# opendeck_mini.net
KiCad netlist of a schematic drawn in EAGLE
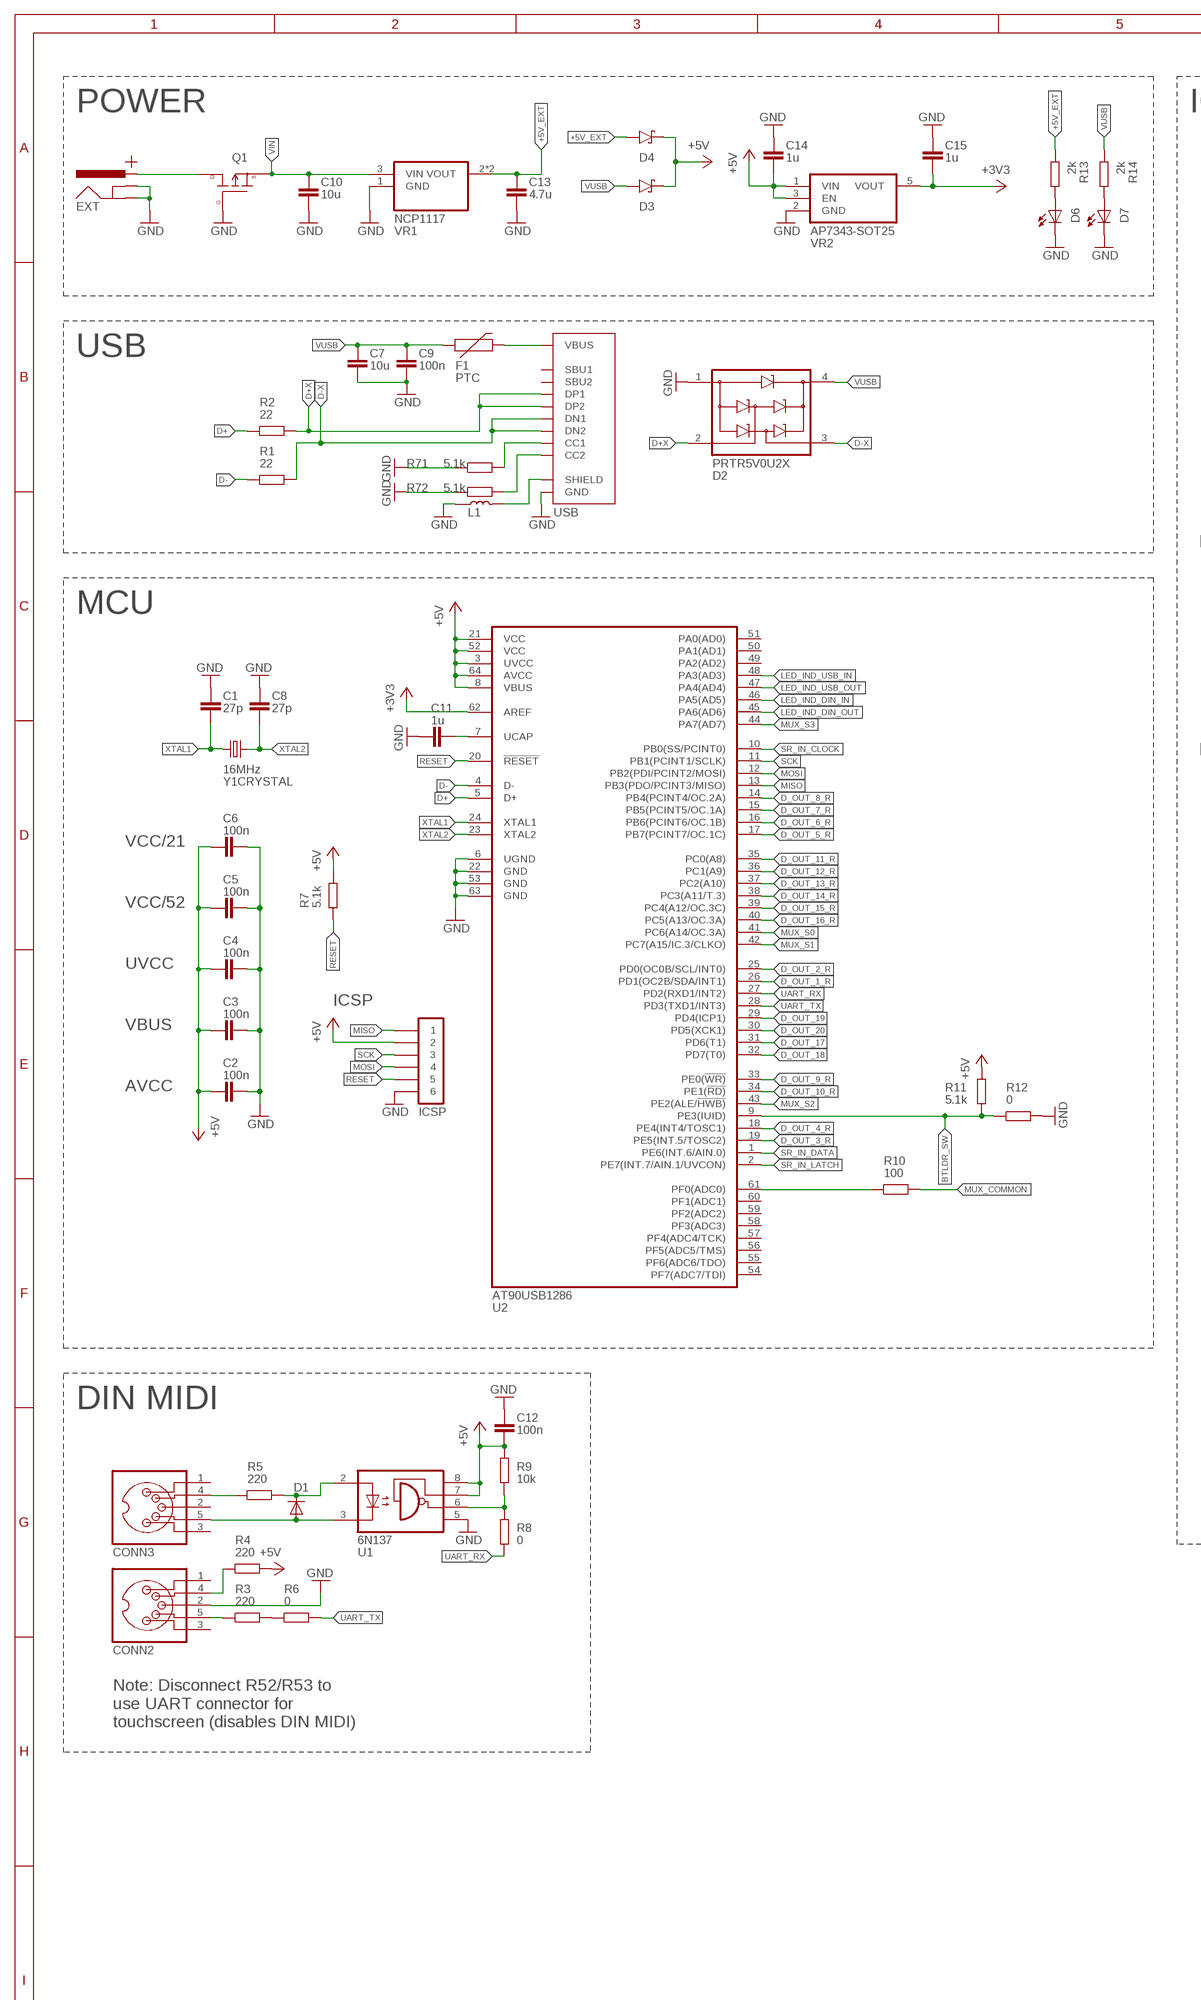
[diagram p0: schematic, sheet 1, part 1 of 2]
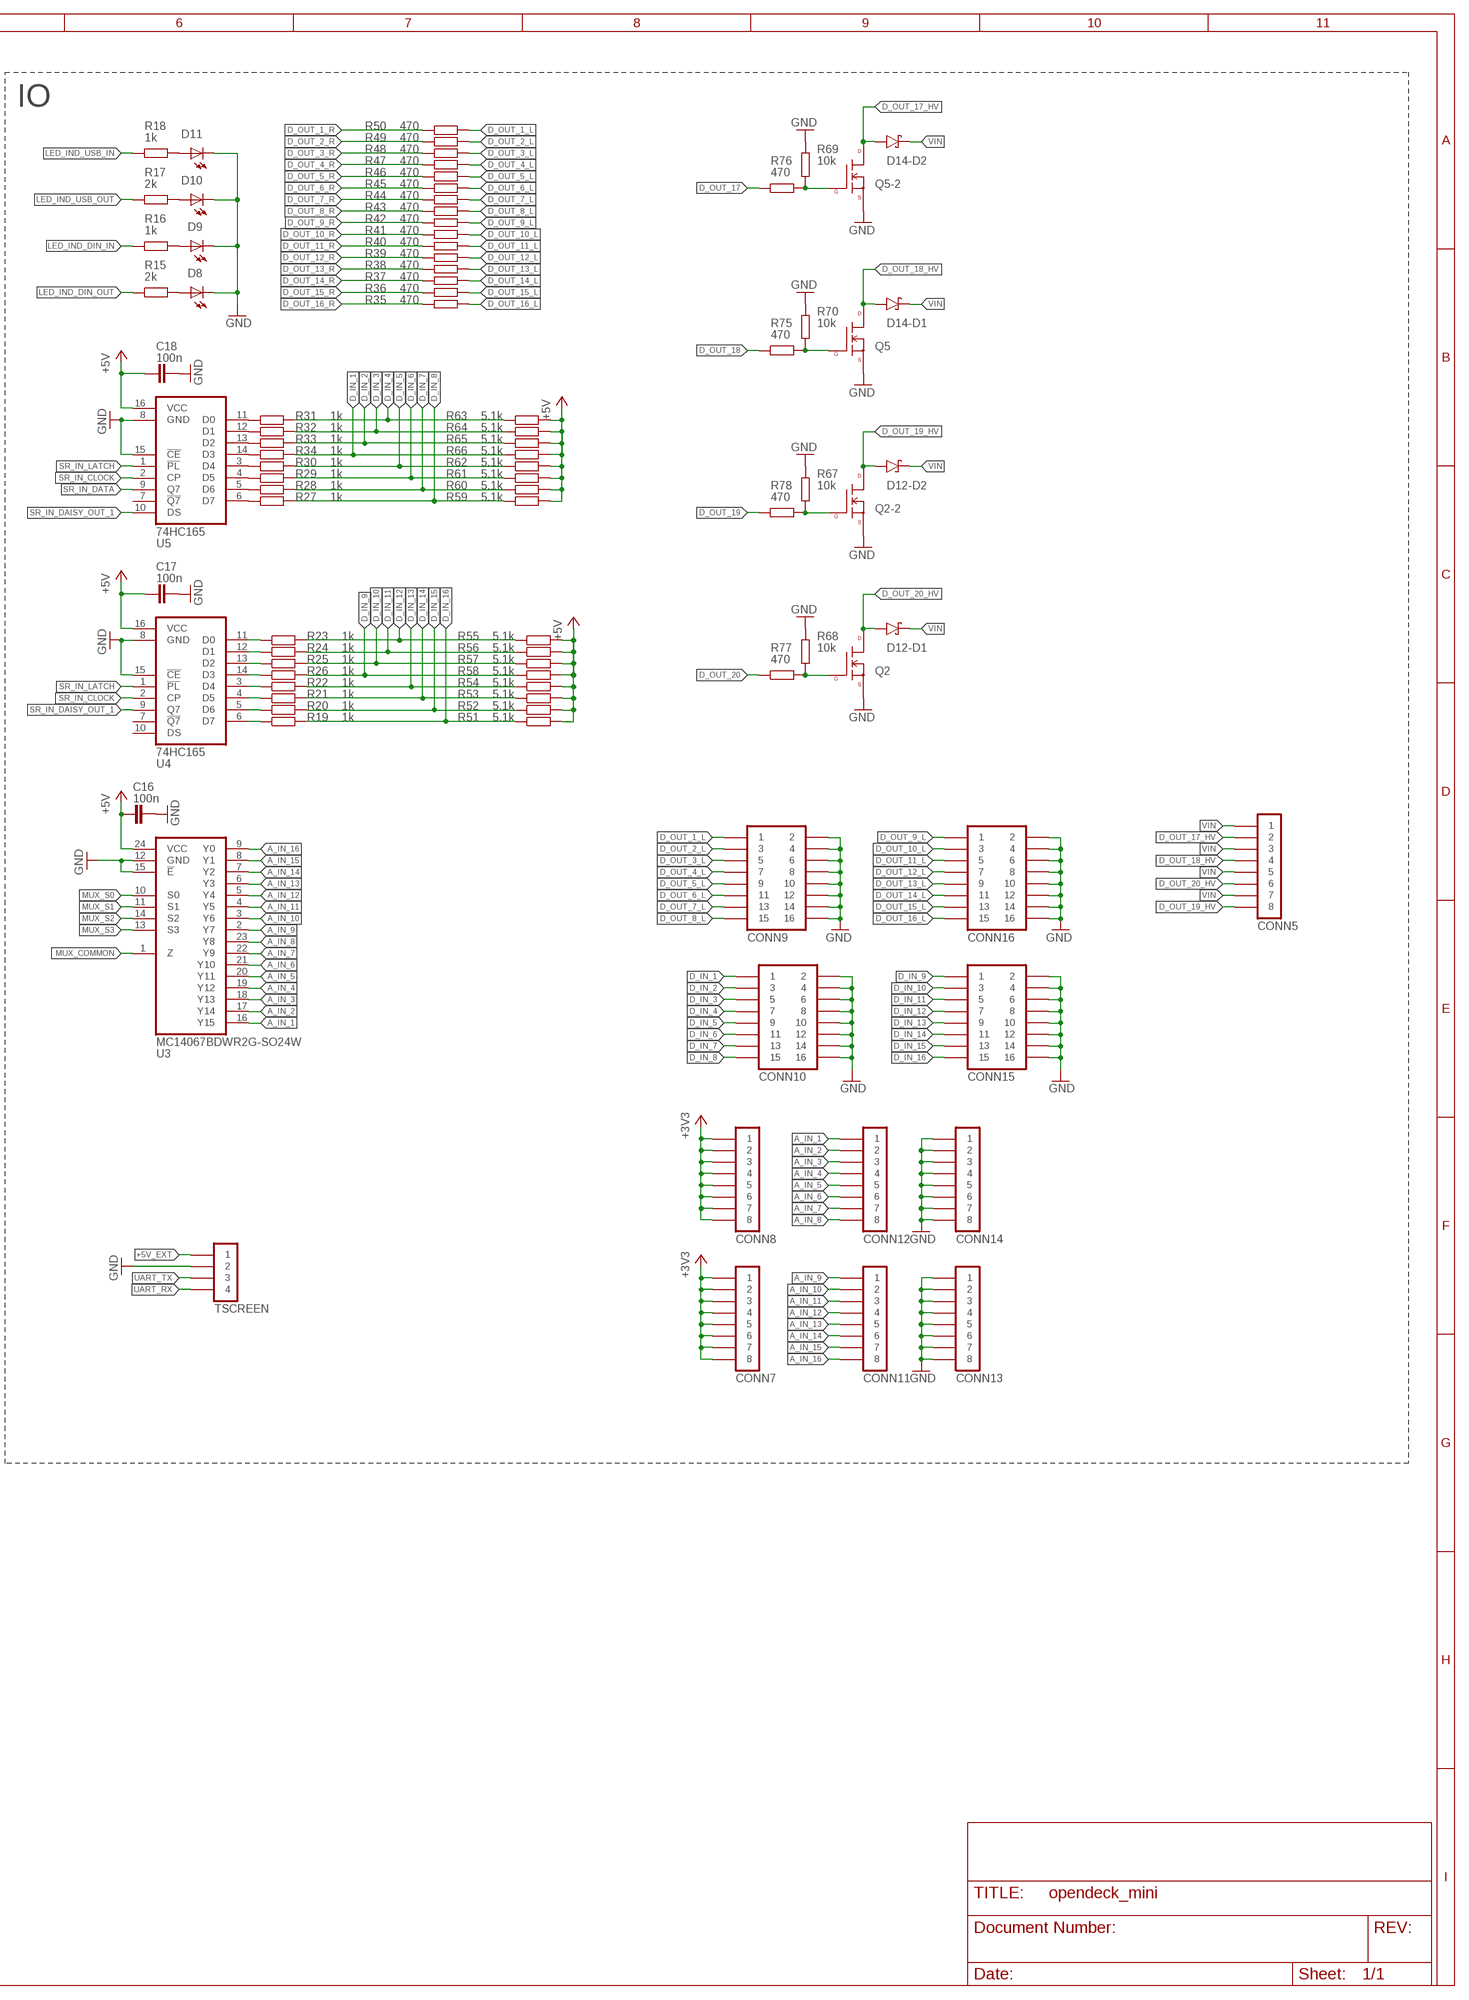
[diagram p1: schematic, sheet 1, part 2 of 2]

(export (version "E")
  (design (tool "Eeschema 10.0.6"))
  (components
    (comp (ref "C1")
      (value "27p")
      (footprint "eagle-import:C0402")
      (libsource (lib "eagle-import") (part "CAPACITOR-0402"))
    )
    (comp (ref "C2")
      (value "100n")
      (footprint "eagle-import:C0402")
      (libsource (lib "eagle-import") (part "CAPACITOR-0402"))
    )
    (comp (ref "C3")
      (value "100n")
      (footprint "eagle-import:C0402")
      (libsource (lib "eagle-import") (part "CAPACITOR-0402"))
    )
    (comp (ref "C4")
      (value "100n")
      (footprint "eagle-import:C0402")
      (libsource (lib "eagle-import") (part "CAPACITOR-0402"))
    )
    (comp (ref "C5")
      (value "100n")
      (footprint "eagle-import:C0402")
      (libsource (lib "eagle-import") (part "CAPACITOR-0402"))
    )
    (comp (ref "C6")
      (value "100n")
      (footprint "eagle-import:C0402")
      (libsource (lib "eagle-import") (part "CAPACITOR-0402"))
    )
    (comp (ref "C7")
      (value "10u")
      (footprint "eagle-import:C0805")
      (libsource (lib "eagle-import") (part "CAPACITOR-0805"))
    )
    (comp (ref "C8")
      (value "27p")
      (footprint "eagle-import:C0402")
      (libsource (lib "eagle-import") (part "CAPACITOR-0402"))
    )
    (comp (ref "C9")
      (value "100n")
      (footprint "eagle-import:C0402")
      (libsource (lib "eagle-import") (part "CAPACITOR-0402"))
    )
    (comp (ref "C10")
      (value "10u")
      (footprint "eagle-import:C0805")
      (libsource (lib "eagle-import") (part "CAPACITOR-0805"))
    )
    (comp (ref "C11")
      (value "1u")
      (footprint "eagle-import:C0603")
      (libsource (lib "eagle-import") (part "CAPACITOR-0603"))
    )
    (comp (ref "C12")
      (value "100n")
      (footprint "eagle-import:C0402")
      (libsource (lib "eagle-import") (part "CAPACITOR-0402"))
    )
    (comp (ref "C13")
      (value "4.7u")
      (footprint "eagle-import:C0603")
      (libsource (lib "eagle-import") (part "CAPACITOR-0603"))
    )
    (comp (ref "C14")
      (value "1u")
      (footprint "eagle-import:C0603")
      (libsource (lib "eagle-import") (part "CAPACITOR-0603"))
    )
    (comp (ref "C15")
      (value "1u")
      (footprint "eagle-import:C0603")
      (libsource (lib "eagle-import") (part "CAPACITOR-0603"))
    )
    (comp (ref "C16")
      (value "100n")
      (footprint "eagle-import:C0402")
      (libsource (lib "eagle-import") (part "CAPACITOR-0402"))
    )
    (comp (ref "C17")
      (value "100n")
      (footprint "eagle-import:C0402")
      (libsource (lib "eagle-import") (part "CAPACITOR-0402"))
    )
    (comp (ref "C18")
      (value "100n")
      (footprint "eagle-import:C0402")
      (libsource (lib "eagle-import") (part "CAPACITOR-0402"))
    )
    (comp (ref "CONN2")
      (value "MIDI_CONN-STD")
      (footprint "eagle-import:DIN5")
      (fields (field (name "MANUFACTURER") "Switchcraft") (field (name "MPN") "57PC5F"))
      (libsource (lib "eagle-import") (part "MIDI_CONN-STD"))
    )
    (comp (ref "CONN3")
      (value "MIDI_CONN-STD")
      (footprint "eagle-import:DIN5")
      (fields (field (name "MANUFACTURER") "Switchcraft") (field (name "MPN") "57PC5F"))
      (libsource (lib "eagle-import") (part "MIDI_CONN-STD"))
    )
    (comp (ref "CONN5")
      (value "PINHD-1X08")
      (footprint "eagle-import:PHOENIX_CONTACT-1984675")
      (fields (field (name "MANUFACTURER") "Phoenix Contact") (field (name "MPN") "1984675"))
      (libsource (lib "eagle-import") (part "PINHD-1X08"))
    )
    (comp (ref "CONN7")
      (value "PINHD-1X08-TH-2.54MM")
      (footprint "eagle-import:1X08-2.54")
      (libsource (lib "eagle-import") (part "PINHD-1X08-TH-2.54MM"))
    )
    (comp (ref "CONN8")
      (value "PINHD-1X08-TH-2.54MM")
      (footprint "eagle-import:1X08-2.54")
      (libsource (lib "eagle-import") (part "PINHD-1X08-TH-2.54MM"))
    )
    (comp (ref "CONN9")
      (value "PINHD-2X08-TH-2.54MM")
      (footprint "eagle-import:2X08-2.54")
      (libsource (lib "eagle-import") (part "PINHD-2X08-TH-2.54MM"))
    )
    (comp (ref "CONN10")
      (value "PINHD-2X08-TH-2.54MM")
      (footprint "eagle-import:2X08-2.54")
      (libsource (lib "eagle-import") (part "PINHD-2X08-TH-2.54MM"))
    )
    (comp (ref "CONN11")
      (value "PINHD-1X08-TH-2.54MM")
      (footprint "eagle-import:1X08-2.54")
      (libsource (lib "eagle-import") (part "PINHD-1X08-TH-2.54MM"))
    )
    (comp (ref "CONN12")
      (value "PINHD-1X08-TH-2.54MM")
      (footprint "eagle-import:1X08-2.54")
      (libsource (lib "eagle-import") (part "PINHD-1X08-TH-2.54MM"))
    )
    (comp (ref "CONN13")
      (value "PINHD-1X08-TH-2.54MM")
      (footprint "eagle-import:1X08-2.54")
      (libsource (lib "eagle-import") (part "PINHD-1X08-TH-2.54MM"))
    )
    (comp (ref "CONN14")
      (value "PINHD-1X08-TH-2.54MM")
      (footprint "eagle-import:1X08-2.54")
      (libsource (lib "eagle-import") (part "PINHD-1X08-TH-2.54MM"))
    )
    (comp (ref "CONN15")
      (value "PINHD-2X08-TH-2.54MM")
      (footprint "eagle-import:2X08-2.54")
      (libsource (lib "eagle-import") (part "PINHD-2X08-TH-2.54MM"))
    )
    (comp (ref "CONN16")
      (value "PINHD-2X08-TH-2.54MM")
      (footprint "eagle-import:2X08-2.54")
      (libsource (lib "eagle-import") (part "PINHD-2X08-TH-2.54MM"))
    )
    (comp (ref "D1")
      (value "1N4148")
      (footprint "eagle-import:SOD-323")
      (fields (field (name "MANUFACTURER") "Comchip Technology") (field (name "MPN") "1N4148WS-HF"))
      (libsource (lib "eagle-import") (part "DIODE-SOD323"))
    )
    (comp (ref "D2")
      (value "PRTR5V0U2X")
      (footprint "eagle-import:SOT143")
      (fields (field (name "MANUFACTURER") "Nexperia"))
      (libsource (lib "eagle-import") (part "PRTR5V0U2X"))
    )
    (comp (ref "D3")
      (value "BAT46INFEON-SOD123")
      (footprint "eagle-import:SOD-123")
      (fields (field (name "MANUFACTURER") "Infineon Technologies") (field (name "MPN") "BAT60AE6327HTSA1"))
      (libsource (lib "eagle-import") (part "BAT46-SOD123INFEON"))
    )
    (comp (ref "D4")
      (value "BAT46INFEON-SOD123")
      (footprint "eagle-import:SOD-123")
      (fields (field (name "MANUFACTURER") "Infineon Technologies") (field (name "MPN") "BAT60AE6327HTSA1"))
      (libsource (lib "eagle-import") (part "BAT46-SOD123INFEON"))
    )
    (comp (ref "D6")
      (value "Green")
      (footprint "eagle-import:0805_LED")
      (libsource (lib "eagle-import") (part "LED-0805"))
    )
    (comp (ref "D7")
      (value "Blue")
      (footprint "eagle-import:0805_LED")
      (libsource (lib "eagle-import") (part "LED-0805"))
    )
    (comp (ref "D8")
      (value "Red")
      (footprint "eagle-import:0805_LED")
      (libsource (lib "eagle-import") (part "LED-0805"))
    )
    (comp (ref "D9")
      (value "Yellow")
      (footprint "eagle-import:0805_LED")
      (libsource (lib "eagle-import") (part "LED-0805"))
    )
    (comp (ref "D10")
      (value "Red")
      (footprint "eagle-import:0805_LED")
      (libsource (lib "eagle-import") (part "LED-0805"))
    )
    (comp (ref "D11")
      (value "Yellow")
      (footprint "eagle-import:0805_LED")
      (libsource (lib "eagle-import") (part "LED-0805"))
    )
    (comp (ref "D12")
      (value "BAS7007E6327HTSA1")
      (footprint "eagle-import:SOT143")
      (libsource (lib "eagle-import") (part "BAS7007E6327HTSA1"))
    )
    (comp (ref "D14")
      (value "BAS7007E6327HTSA1")
      (footprint "eagle-import:SOT143")
      (libsource (lib "eagle-import") (part "BAS7007E6327HTSA1"))
    )
    (comp (ref "EXT")
      (value "BARREL_JACK")
      (footprint "eagle-import:BARREL_JACK")
      (fields (field (name "MANUFACTURER") "Gravitech") (field (name "MPN") "CON-SOCJ-2155"))
      (libsource (lib "eagle-import") (part "BARREL_JACK"))
    )
    (comp (ref "F1")
      (value "PTC")
      (footprint "eagle-import:L1812")
      (fields (field (name "MANUFACTURER") "Bourns") (field (name "MPN") "MF-MSMF050-2"))
      (libsource (lib "eagle-import") (part "PTC"))
    )
    (comp (ref "ICSP")
      (value "PINHD-2X03-TH-2.54MM-V")
      (footprint "eagle-import:2X03-2.54-V")
      (libsource (lib "eagle-import") (part "PINHD-2X03-TH-2.54MM-V"))
    )
    (comp (ref "L1")
      (value "FERRITE_BEAD-BLM21PG221SN1D")
      (footprint "eagle-import:L0805")
      (fields (field (name "MANUFACTURER") "Murata") (field (name "MPN") "BLM21PG221SN1D"))
      (libsource (lib "eagle-import") (part "FERRITE_BEAD-BLM21PG221SN1D"))
    )
    (comp (ref "Q1")
      (value "BSS314PEH6327XTSA1")
      (footprint "eagle-import:SOT23")
      (fields (field (name "MANUFACTURER") "Infineon Technologies"))
      (libsource (lib "eagle-import") (part "BSS314PEH6327XTSA1"))
    )
    (comp (ref "Q2")
      (value "NTGD3148N")
      (footprint "eagle-import:TSOP-6")
      (fields (field (name "MANUFACTURER") "ON Semiconductor") (field (name "MPN") "NTGD3148NT1G"))
      (libsource (lib "eagle-import") (part "NTGD3148N"))
    )
    (comp (ref "Q5")
      (value "NTGD3148N")
      (footprint "eagle-import:TSOP-6")
      (fields (field (name "MANUFACTURER") "ON Semiconductor") (field (name "MPN") "NTGD3148NT1G"))
      (libsource (lib "eagle-import") (part "NTGD3148N"))
    )
    (comp (ref "R1")
      (value "22")
      (footprint "eagle-import:R0402")
      (libsource (lib "eagle-import") (part "RESISTOR-0402"))
    )
    (comp (ref "R2")
      (value "22")
      (footprint "eagle-import:R0402")
      (libsource (lib "eagle-import") (part "RESISTOR-0402"))
    )
    (comp (ref "R3")
      (value "220")
      (footprint "eagle-import:R0402")
      (libsource (lib "eagle-import") (part "RESISTOR-0402"))
    )
    (comp (ref "R4")
      (value "220")
      (footprint "eagle-import:R0402")
      (libsource (lib "eagle-import") (part "RESISTOR-0402"))
    )
    (comp (ref "R5")
      (value "220")
      (footprint "eagle-import:R0402")
      (libsource (lib "eagle-import") (part "RESISTOR-0402"))
    )
    (comp (ref "R6")
      (value "0")
      (footprint "eagle-import:1X02-2.54-V")
      (libsource (lib "eagle-import") (part "RESISTOR-TH-2.54"))
    )
    (comp (ref "R7")
      (value "5.1k")
      (footprint "eagle-import:R0402")
      (libsource (lib "eagle-import") (part "RESISTOR-0402"))
    )
    (comp (ref "R8")
      (value "0")
      (footprint "eagle-import:1X02-2.54-V")
      (libsource (lib "eagle-import") (part "RESISTOR-TH-2.54"))
    )
    (comp (ref "R9")
      (value "10k")
      (footprint "eagle-import:R0402")
      (libsource (lib "eagle-import") (part "RESISTOR-0402"))
    )
    (comp (ref "R10")
      (value "100")
      (footprint "eagle-import:R0402")
      (libsource (lib "eagle-import") (part "RESISTOR-0402"))
    )
    (comp (ref "R11")
      (value "5.1k")
      (footprint "eagle-import:R0402")
      (libsource (lib "eagle-import") (part "RESISTOR-0402"))
    )
    (comp (ref "R12")
      (value "0")
      (footprint "eagle-import:1X02-2.54-V")
      (libsource (lib "eagle-import") (part "RESISTOR-TH-2.54"))
    )
    (comp (ref "R13")
      (value "2k")
      (footprint "eagle-import:R0402")
      (libsource (lib "eagle-import") (part "RESISTOR-0402"))
    )
    (comp (ref "R14")
      (value "2k")
      (footprint "eagle-import:R0402")
      (libsource (lib "eagle-import") (part "RESISTOR-0402"))
    )
    (comp (ref "R15")
      (value "2k")
      (footprint "eagle-import:R0402")
      (libsource (lib "eagle-import") (part "RESISTOR-0402"))
    )
    (comp (ref "R16")
      (value "1k")
      (footprint "eagle-import:R0402")
      (libsource (lib "eagle-import") (part "RESISTOR-0402"))
    )
    (comp (ref "R17")
      (value "2k")
      (footprint "eagle-import:R0402")
      (libsource (lib "eagle-import") (part "RESISTOR-0402"))
    )
    (comp (ref "R18")
      (value "1k")
      (footprint "eagle-import:R0402")
      (libsource (lib "eagle-import") (part "RESISTOR-0402"))
    )
    (comp (ref "R19")
      (value "1k")
      (footprint "eagle-import:R0402")
      (libsource (lib "eagle-import") (part "RESISTOR-0402"))
    )
    (comp (ref "R20")
      (value "1k")
      (footprint "eagle-import:R0402")
      (libsource (lib "eagle-import") (part "RESISTOR-0402"))
    )
    (comp (ref "R21")
      (value "1k")
      (footprint "eagle-import:R0402")
      (libsource (lib "eagle-import") (part "RESISTOR-0402"))
    )
    (comp (ref "R22")
      (value "1k")
      (footprint "eagle-import:R0402")
      (libsource (lib "eagle-import") (part "RESISTOR-0402"))
    )
    (comp (ref "R23")
      (value "1k")
      (footprint "eagle-import:R0402")
      (libsource (lib "eagle-import") (part "RESISTOR-0402"))
    )
    (comp (ref "R24")
      (value "1k")
      (footprint "eagle-import:R0402")
      (libsource (lib "eagle-import") (part "RESISTOR-0402"))
    )
    (comp (ref "R25")
      (value "1k")
      (footprint "eagle-import:R0402")
      (libsource (lib "eagle-import") (part "RESISTOR-0402"))
    )
    (comp (ref "R26")
      (value "1k")
      (footprint "eagle-import:R0402")
      (libsource (lib "eagle-import") (part "RESISTOR-0402"))
    )
    (comp (ref "R27")
      (value "1k")
      (footprint "eagle-import:R0402")
      (libsource (lib "eagle-import") (part "RESISTOR-0402"))
    )
    (comp (ref "R28")
      (value "1k")
      (footprint "eagle-import:R0402")
      (libsource (lib "eagle-import") (part "RESISTOR-0402"))
    )
    (comp (ref "R29")
      (value "1k")
      (footprint "eagle-import:R0402")
      (libsource (lib "eagle-import") (part "RESISTOR-0402"))
    )
    (comp (ref "R30")
      (value "1k")
      (footprint "eagle-import:R0402")
      (libsource (lib "eagle-import") (part "RESISTOR-0402"))
    )
    (comp (ref "R31")
      (value "1k")
      (footprint "eagle-import:R0402")
      (libsource (lib "eagle-import") (part "RESISTOR-0402"))
    )
    (comp (ref "R32")
      (value "1k")
      (footprint "eagle-import:R0402")
      (libsource (lib "eagle-import") (part "RESISTOR-0402"))
    )
    (comp (ref "R33")
      (value "1k")
      (footprint "eagle-import:R0402")
      (libsource (lib "eagle-import") (part "RESISTOR-0402"))
    )
    (comp (ref "R34")
      (value "1k")
      (footprint "eagle-import:R0402")
      (libsource (lib "eagle-import") (part "RESISTOR-0402"))
    )
    (comp (ref "R35")
      (value "470")
      (footprint "eagle-import:R0402")
      (libsource (lib "eagle-import") (part "RESISTOR-0402"))
    )
    (comp (ref "R36")
      (value "470")
      (footprint "eagle-import:R0402")
      (libsource (lib "eagle-import") (part "RESISTOR-0402"))
    )
    (comp (ref "R37")
      (value "470")
      (footprint "eagle-import:R0402")
      (libsource (lib "eagle-import") (part "RESISTOR-0402"))
    )
    (comp (ref "R38")
      (value "470")
      (footprint "eagle-import:R0402")
      (libsource (lib "eagle-import") (part "RESISTOR-0402"))
    )
    (comp (ref "R39")
      (value "470")
      (footprint "eagle-import:R0402")
      (libsource (lib "eagle-import") (part "RESISTOR-0402"))
    )
    (comp (ref "R40")
      (value "470")
      (footprint "eagle-import:R0402")
      (libsource (lib "eagle-import") (part "RESISTOR-0402"))
    )
    (comp (ref "R41")
      (value "470")
      (footprint "eagle-import:R0402")
      (libsource (lib "eagle-import") (part "RESISTOR-0402"))
    )
    (comp (ref "R42")
      (value "470")
      (footprint "eagle-import:R0402")
      (libsource (lib "eagle-import") (part "RESISTOR-0402"))
    )
    (comp (ref "R43")
      (value "470")
      (footprint "eagle-import:R0402")
      (libsource (lib "eagle-import") (part "RESISTOR-0402"))
    )
    (comp (ref "R44")
      (value "470")
      (footprint "eagle-import:R0402")
      (libsource (lib "eagle-import") (part "RESISTOR-0402"))
    )
    (comp (ref "R45")
      (value "470")
      (footprint "eagle-import:R0402")
      (libsource (lib "eagle-import") (part "RESISTOR-0402"))
    )
    (comp (ref "R46")
      (value "470")
      (footprint "eagle-import:R0402")
      (libsource (lib "eagle-import") (part "RESISTOR-0402"))
    )
    (comp (ref "R47")
      (value "470")
      (footprint "eagle-import:R0402")
      (libsource (lib "eagle-import") (part "RESISTOR-0402"))
    )
    (comp (ref "R48")
      (value "470")
      (footprint "eagle-import:R0402")
      (libsource (lib "eagle-import") (part "RESISTOR-0402"))
    )
    (comp (ref "R49")
      (value "470")
      (footprint "eagle-import:R0402")
      (libsource (lib "eagle-import") (part "RESISTOR-0402"))
    )
    (comp (ref "R50")
      (value "470")
      (footprint "eagle-import:R0402")
      (libsource (lib "eagle-import") (part "RESISTOR-0402"))
    )
    (comp (ref "R51")
      (value "5.1k")
      (footprint "eagle-import:R0402")
      (libsource (lib "eagle-import") (part "RESISTOR-0402"))
    )
    (comp (ref "R52")
      (value "5.1k")
      (footprint "eagle-import:R0402")
      (libsource (lib "eagle-import") (part "RESISTOR-0402"))
    )
    (comp (ref "R53")
      (value "5.1k")
      (footprint "eagle-import:R0402")
      (libsource (lib "eagle-import") (part "RESISTOR-0402"))
    )
    (comp (ref "R54")
      (value "5.1k")
      (footprint "eagle-import:R0402")
      (libsource (lib "eagle-import") (part "RESISTOR-0402"))
    )
    (comp (ref "R55")
      (value "5.1k")
      (footprint "eagle-import:R0402")
      (libsource (lib "eagle-import") (part "RESISTOR-0402"))
    )
    (comp (ref "R56")
      (value "5.1k")
      (footprint "eagle-import:R0402")
      (libsource (lib "eagle-import") (part "RESISTOR-0402"))
    )
    (comp (ref "R57")
      (value "5.1k")
      (footprint "eagle-import:R0402")
      (libsource (lib "eagle-import") (part "RESISTOR-0402"))
    )
    (comp (ref "R58")
      (value "5.1k")
      (footprint "eagle-import:R0402")
      (libsource (lib "eagle-import") (part "RESISTOR-0402"))
    )
    (comp (ref "R59")
      (value "5.1k")
      (footprint "eagle-import:R0402")
      (libsource (lib "eagle-import") (part "RESISTOR-0402"))
    )
    (comp (ref "R60")
      (value "5.1k")
      (footprint "eagle-import:R0402")
      (libsource (lib "eagle-import") (part "RESISTOR-0402"))
    )
    (comp (ref "R61")
      (value "5.1k")
      (footprint "eagle-import:R0402")
      (libsource (lib "eagle-import") (part "RESISTOR-0402"))
    )
    (comp (ref "R62")
      (value "5.1k")
      (footprint "eagle-import:R0402")
      (libsource (lib "eagle-import") (part "RESISTOR-0402"))
    )
    (comp (ref "R63")
      (value "5.1k")
      (footprint "eagle-import:R0402")
      (libsource (lib "eagle-import") (part "RESISTOR-0402"))
    )
    (comp (ref "R64")
      (value "5.1k")
      (footprint "eagle-import:R0402")
      (libsource (lib "eagle-import") (part "RESISTOR-0402"))
    )
    (comp (ref "R65")
      (value "5.1k")
      (footprint "eagle-import:R0402")
      (libsource (lib "eagle-import") (part "RESISTOR-0402"))
    )
    (comp (ref "R66")
      (value "5.1k")
      (footprint "eagle-import:R0402")
      (libsource (lib "eagle-import") (part "RESISTOR-0402"))
    )
    (comp (ref "R67")
      (value "10k")
      (footprint "eagle-import:R0402")
      (libsource (lib "eagle-import") (part "RESISTOR-0402"))
    )
    (comp (ref "R68")
      (value "10k")
      (footprint "eagle-import:R0402")
      (libsource (lib "eagle-import") (part "RESISTOR-0402"))
    )
    (comp (ref "R69")
      (value "10k")
      (footprint "eagle-import:R0402")
      (libsource (lib "eagle-import") (part "RESISTOR-0402"))
    )
    (comp (ref "R70")
      (value "10k")
      (footprint "eagle-import:R0402")
      (libsource (lib "eagle-import") (part "RESISTOR-0402"))
    )
    (comp (ref "R71")
      (value "5.1k")
      (footprint "eagle-import:R0402")
      (libsource (lib "eagle-import") (part "RESISTOR-0402"))
    )
    (comp (ref "R72")
      (value "5.1k")
      (footprint "eagle-import:R0402")
      (libsource (lib "eagle-import") (part "RESISTOR-0402"))
    )
    (comp (ref "R75")
      (value "470")
      (footprint "eagle-import:R0402")
      (libsource (lib "eagle-import") (part "RESISTOR-0402"))
    )
    (comp (ref "R76")
      (value "470")
      (footprint "eagle-import:R0402")
      (libsource (lib "eagle-import") (part "RESISTOR-0402"))
    )
    (comp (ref "R77")
      (value "470")
      (footprint "eagle-import:R0402")
      (libsource (lib "eagle-import") (part "RESISTOR-0402"))
    )
    (comp (ref "R78")
      (value "470")
      (footprint "eagle-import:R0402")
      (libsource (lib "eagle-import") (part "RESISTOR-0402"))
    )
    (comp (ref "TSCREEN")
      (value "PINHD-1X04-TH-2.54MM")
      (footprint "eagle-import:1X04-2.54")
      (libsource (lib "eagle-import") (part "PINHD-1X04-TH-2.54MM"))
    )
    (comp (ref "U1")
      (value "6N137")
      (footprint "eagle-import:DIL08")
      (fields (field (name "MANUFACTURER") "Vishay"))
      (libsource (lib "eagle-import") (part "6N137"))
    )
    (comp (ref "U2")
      (value "AT90USB1286")
      (footprint "eagle-import:TQFP-64-14X14")
      (fields (field (name "MANUFACTURER") "Microchip/Atmel") (field (name "MPN") "AT90USB1286-AU"))
      (libsource (lib "eagle-import") (part "AT90USB1286"))
    )
    (comp (ref "U3")
      (value "MC14067BDWR2G-SO24W")
      (footprint "eagle-import:SO24-W")
      (fields (field (name "MANUFACTURER") "ON Semiconductor") (field (name "MPN") "MC14067BDWR2G"))
      (libsource (lib "eagle-import") (part "MC14067BDWR2G-SO24W"))
    )
    (comp (ref "U4")
      (value "74HC165")
      (footprint "eagle-import:SO16")
      (fields (field (name "MANUFACTURER") "Nexperia") (field (name "MPN") "74HC165D"))
      (libsource (lib "eagle-import") (part "74165HC"))
    )
    (comp (ref "U5")
      (value "74HC165")
      (footprint "eagle-import:SO16")
      (fields (field (name "MANUFACTURER") "Nexperia") (field (name "MPN") "74HC165D"))
      (libsource (lib "eagle-import") (part "74165HC"))
    )
    (comp (ref "USB")
      (value "USB-C")
      (footprint "eagle-import:GCT-USB4085-GF-A")
      (fields (field (name "MANUFACTURER") "GCT") (field (name "MPN") "USB4085-GF-A"))
      (libsource (lib "eagle-import") (part "USB-C"))
    )
    (comp (ref "VR1")
      (value "NCP1117")
      (footprint "eagle-import:SOT223")
      (fields (field (name "MANUFACTURER") "ON Semiconductor") (field (name "MPN") "NCP1117ST50T3G"))
      (libsource (lib "eagle-import") (part "NCP1117"))
    )
    (comp (ref "VR2")
      (value "AP7343-SOT25")
      (footprint "eagle-import:SOT25")
      (fields (field (name "MANUFACTURER") "Diodes Incorporated") (field (name "MPN") "AP7343-33W5-7"))
      (libsource (lib "eagle-import") (part "AP7343-SOT25"))
    )
    (comp (ref "Y1")
      (value "16MHz")
      (footprint "eagle-import:CRYSTAL-SMD-3.2X2.5")
      (fields (field (name "MANUFACTURER") "Epson") (field (name "MPN") "X1E0000210120 TSX-3225 16MHZ 16PF"))
      (libsource (lib "eagle-import") (part "CRYSTAL-4P-SMD-3.2X2.5"))
    )
  )
  (nets
    (net (code "1") (name "+3V3") (class "Default")
      (node (ref "C15") (pin "2") (pinfunction "2_2") (pintype "passive"))
      (node (ref "CONN7") (pin "1") (pinfunction "1_1") (pintype "passive"))
      (node (ref "CONN7") (pin "2") (pinfunction "2_2") (pintype "passive"))
      (node (ref "CONN7") (pin "3") (pinfunction "3_3") (pintype "passive"))
      (node (ref "CONN7") (pin "4") (pinfunction "4_4") (pintype "passive"))
      (node (ref "CONN7") (pin "5") (pinfunction "5_5") (pintype "passive"))
      (node (ref "CONN7") (pin "6") (pinfunction "6_6") (pintype "passive"))
      (node (ref "CONN7") (pin "7") (pinfunction "7_7") (pintype "passive"))
      (node (ref "CONN7") (pin "8") (pinfunction "8_8") (pintype "passive"))
      (node (ref "CONN8") (pin "1") (pinfunction "1_1") (pintype "passive"))
      (node (ref "CONN8") (pin "2") (pinfunction "2_2") (pintype "passive"))
      (node (ref "CONN8") (pin "3") (pinfunction "3_3") (pintype "passive"))
      (node (ref "CONN8") (pin "4") (pinfunction "4_4") (pintype "passive"))
      (node (ref "CONN8") (pin "5") (pinfunction "5_5") (pintype "passive"))
      (node (ref "CONN8") (pin "6") (pinfunction "6_6") (pintype "passive"))
      (node (ref "CONN8") (pin "7") (pinfunction "7_7") (pintype "passive"))
      (node (ref "CONN8") (pin "8") (pinfunction "8_8") (pintype "passive"))
      (node (ref "U2") (pin "62") (pinfunction "AREF_62") (pintype "power_in"))
      (node (ref "VR2") (pin "5") (pinfunction "VOUT_5") (pintype "passive"))
    )
    (net (code "2") (name "+5V") (class "Default")
      (node (ref "C12") (pin "2") (pinfunction "2_2") (pintype "passive"))
      (node (ref "C14") (pin "2") (pinfunction "2_2") (pintype "passive"))
      (node (ref "C16") (pin "1") (pinfunction "1_1") (pintype "passive"))
      (node (ref "C17") (pin "1") (pinfunction "1_1") (pintype "passive"))
      (node (ref "C18") (pin "1") (pinfunction "1_1") (pintype "passive"))
      (node (ref "C2") (pin "1") (pinfunction "1_1") (pintype "passive"))
      (node (ref "C3") (pin "1") (pinfunction "1_1") (pintype "passive"))
      (node (ref "C4") (pin "1") (pinfunction "1_1") (pintype "passive"))
      (node (ref "C5") (pin "1") (pinfunction "1_1") (pintype "passive"))
      (node (ref "C6") (pin "1") (pinfunction "1_1") (pintype "passive"))
      (node (ref "D3") (pin "C") (pinfunction "C_C") (pintype "passive"))
      (node (ref "D4") (pin "C") (pinfunction "C_C") (pintype "passive"))
      (node (ref "ICSP") (pin "2") (pinfunction "2_2") (pintype "passive"))
      (node (ref "R11") (pin "2") (pinfunction "2_2") (pintype "passive"))
      (node (ref "R4") (pin "2") (pinfunction "2_2") (pintype "passive"))
      (node (ref "R51") (pin "2") (pinfunction "2_2") (pintype "passive"))
      (node (ref "R52") (pin "2") (pinfunction "2_2") (pintype "passive"))
      (node (ref "R53") (pin "2") (pinfunction "2_2") (pintype "passive"))
      (node (ref "R54") (pin "2") (pinfunction "2_2") (pintype "passive"))
      (node (ref "R55") (pin "2") (pinfunction "2_2") (pintype "passive"))
      (node (ref "R56") (pin "2") (pinfunction "2_2") (pintype "passive"))
      (node (ref "R57") (pin "2") (pinfunction "2_2") (pintype "passive"))
      (node (ref "R58") (pin "2") (pinfunction "2_2") (pintype "passive"))
      (node (ref "R59") (pin "2") (pinfunction "2_2") (pintype "passive"))
      (node (ref "R60") (pin "2") (pinfunction "2_2") (pintype "passive"))
      (node (ref "R61") (pin "2") (pinfunction "2_2") (pintype "passive"))
      (node (ref "R62") (pin "2") (pinfunction "2_2") (pintype "passive"))
      (node (ref "R63") (pin "2") (pinfunction "2_2") (pintype "passive"))
      (node (ref "R64") (pin "2") (pinfunction "2_2") (pintype "passive"))
      (node (ref "R65") (pin "2") (pinfunction "2_2") (pintype "passive"))
      (node (ref "R66") (pin "2") (pinfunction "2_2") (pintype "passive"))
      (node (ref "R7") (pin "2") (pinfunction "2_2") (pintype "passive"))
      (node (ref "R9") (pin "2") (pinfunction "2_2") (pintype "passive"))
      (node (ref "U1") (pin "7") (pinfunction "VE_7") (pintype "input"))
      (node (ref "U1") (pin "8") (pinfunction "VCC_8") (pintype "power_in"))
      (node (ref "U2") (pin "21") (pinfunction "VCC_21") (pintype "power_in"))
      (node (ref "U2") (pin "3") (pinfunction "UVCC_3") (pintype "power_in"))
      (node (ref "U2") (pin "52") (pinfunction "VCC_52") (pintype "power_in"))
      (node (ref "U2") (pin "64") (pinfunction "AVCC_64") (pintype "power_in"))
      (node (ref "U2") (pin "8") (pinfunction "VBUS_8") (pintype "power_in"))
      (node (ref "U3") (pin "24") (pinfunction "VCC_24") (pintype "passive"))
      (node (ref "U4") (pin "16") (pinfunction "VCC_16") (pintype "power_in"))
      (node (ref "U5") (pin "16") (pinfunction "VCC_16") (pintype "power_in"))
      (node (ref "VR2") (pin "1") (pinfunction "VIN_1") (pintype "passive"))
      (node (ref "VR2") (pin "3") (pinfunction "EN_3") (pintype "passive"))
    )
    (net (code "3") (name "+5V_EXT") (class "Default")
      (node (ref "C13") (pin "1") (pinfunction "1_1") (pintype "passive"))
      (node (ref "D4") (pin "A") (pinfunction "A_A") (pintype "passive"))
      (node (ref "R13") (pin "1") (pinfunction "1_1") (pintype "passive"))
      (node (ref "TSCREEN") (pin "1") (pinfunction "1_1") (pintype "passive"))
      (node (ref "VR1") (pin "2") (pinfunction "VOUT_2") (pintype "passive"))
      (node (ref "VR1") (pin "4") (pinfunction "VOUT_4") (pintype "passive"))
    )
    (net (code "4") (name "A_IN_1") (class "Default")
      (node (ref "CONN12") (pin "1") (pinfunction "1_1") (pintype "passive"))
      (node (ref "U3") (pin "16") (pinfunction "Y15_16") (pintype "bidirectional"))
    )
    (net (code "5") (name "A_IN_2") (class "Default")
      (node (ref "CONN12") (pin "2") (pinfunction "2_2") (pintype "passive"))
      (node (ref "U3") (pin "17") (pinfunction "Y14_17") (pintype "bidirectional"))
    )
    (net (code "6") (name "A_IN_3") (class "Default")
      (node (ref "CONN12") (pin "3") (pinfunction "3_3") (pintype "passive"))
      (node (ref "U3") (pin "18") (pinfunction "Y13_18") (pintype "bidirectional"))
    )
    (net (code "7") (name "A_IN_4") (class "Default")
      (node (ref "CONN12") (pin "4") (pinfunction "4_4") (pintype "passive"))
      (node (ref "U3") (pin "19") (pinfunction "Y12_19") (pintype "bidirectional"))
    )
    (net (code "8") (name "A_IN_5") (class "Default")
      (node (ref "CONN12") (pin "5") (pinfunction "5_5") (pintype "passive"))
      (node (ref "U3") (pin "20") (pinfunction "Y11_20") (pintype "bidirectional"))
    )
    (net (code "9") (name "A_IN_6") (class "Default")
      (node (ref "CONN12") (pin "6") (pinfunction "6_6") (pintype "passive"))
      (node (ref "U3") (pin "21") (pinfunction "Y10_21") (pintype "bidirectional"))
    )
    (net (code "10") (name "A_IN_7") (class "Default")
      (node (ref "CONN12") (pin "7") (pinfunction "7_7") (pintype "passive"))
      (node (ref "U3") (pin "22") (pinfunction "Y9_22") (pintype "bidirectional"))
    )
    (net (code "11") (name "A_IN_8") (class "Default")
      (node (ref "CONN12") (pin "8") (pinfunction "8_8") (pintype "passive"))
      (node (ref "U3") (pin "23") (pinfunction "Y8_23") (pintype "bidirectional"))
    )
    (net (code "12") (name "A_IN_9") (class "Default")
      (node (ref "CONN11") (pin "1") (pinfunction "1_1") (pintype "passive"))
      (node (ref "U3") (pin "2") (pinfunction "Y7_2") (pintype "bidirectional"))
    )
    (net (code "13") (name "A_IN_10") (class "Default")
      (node (ref "CONN11") (pin "2") (pinfunction "2_2") (pintype "passive"))
      (node (ref "U3") (pin "3") (pinfunction "Y6_3") (pintype "bidirectional"))
    )
    (net (code "14") (name "A_IN_11") (class "Default")
      (node (ref "CONN11") (pin "3") (pinfunction "3_3") (pintype "passive"))
      (node (ref "U3") (pin "4") (pinfunction "Y5_4") (pintype "bidirectional"))
    )
    (net (code "15") (name "A_IN_12") (class "Default")
      (node (ref "CONN11") (pin "4") (pinfunction "4_4") (pintype "passive"))
      (node (ref "U3") (pin "5") (pinfunction "Y4_5") (pintype "bidirectional"))
    )
    (net (code "16") (name "A_IN_13") (class "Default")
      (node (ref "CONN11") (pin "5") (pinfunction "5_5") (pintype "passive"))
      (node (ref "U3") (pin "6") (pinfunction "Y3_6") (pintype "bidirectional"))
    )
    (net (code "17") (name "A_IN_14") (class "Default")
      (node (ref "CONN11") (pin "6") (pinfunction "6_6") (pintype "passive"))
      (node (ref "U3") (pin "7") (pinfunction "Y2_7") (pintype "bidirectional"))
    )
    (net (code "18") (name "A_IN_15") (class "Default")
      (node (ref "CONN11") (pin "7") (pinfunction "7_7") (pintype "passive"))
      (node (ref "U3") (pin "8") (pinfunction "Y1_8") (pintype "bidirectional"))
    )
    (net (code "19") (name "A_IN_16") (class "Default")
      (node (ref "CONN11") (pin "8") (pinfunction "8_8") (pintype "passive"))
      (node (ref "U3") (pin "9") (pinfunction "Y0_9") (pintype "bidirectional"))
    )
    (net (code "20") (name "BTLDR_SW") (class "Default")
      (node (ref "R11") (pin "1") (pinfunction "1_1") (pintype "passive"))
      (node (ref "R12") (pin "1") (pinfunction "1_1") (pintype "passive"))
      (node (ref "U2") (pin "9") (pinfunction "PE3(IUID)_9") (pintype "bidirectional"))
    )
    (net (code "21") (name "D+") (class "Default")
      (node (ref "R2") (pin "1") (pinfunction "1_1") (pintype "passive"))
      (node (ref "U2") (pin "5") (pinfunction "D+_5") (pintype "bidirectional"))
    )
    (net (code "22") (name "D+X") (class "Default")
      (node (ref "D2") (pin "2") (pinfunction "I/O1_2") (pintype "passive"))
      (node (ref "R2") (pin "2") (pinfunction "2_2") (pintype "passive"))
      (node (ref "USB") (pin "A6") (pinfunction "DP1_A6") (pintype "bidirectional"))
      (node (ref "USB") (pin "B6") (pinfunction "DP2_B6") (pintype "bidirectional"))
    )
    (net (code "23") (name "D-") (class "Default")
      (node (ref "R1") (pin "1") (pinfunction "1_1") (pintype "passive"))
      (node (ref "U2") (pin "4") (pinfunction "D-_4") (pintype "bidirectional"))
    )
    (net (code "24") (name "D-X") (class "Default")
      (node (ref "D2") (pin "3") (pinfunction "I/O2_3") (pintype "passive"))
      (node (ref "R1") (pin "2") (pinfunction "2_2") (pintype "passive"))
      (node (ref "USB") (pin "A7") (pinfunction "DN1_A7") (pintype "bidirectional"))
      (node (ref "USB") (pin "B7") (pinfunction "DN2_B7") (pintype "bidirectional"))
    )
    (net (code "25") (name "D_IN_1") (class "Default")
      (node (ref "CONN10") (pin "1") (pinfunction "1_1") (pintype "passive"))
      (node (ref "R34") (pin "2") (pinfunction "2_2") (pintype "passive"))
      (node (ref "R66") (pin "1") (pinfunction "1_1") (pintype "passive"))
    )
    (net (code "26") (name "D_IN_2") (class "Default")
      (node (ref "CONN10") (pin "3") (pinfunction "3_3") (pintype "passive"))
      (node (ref "R33") (pin "2") (pinfunction "2_2") (pintype "passive"))
      (node (ref "R65") (pin "1") (pinfunction "1_1") (pintype "passive"))
    )
    (net (code "27") (name "D_IN_3") (class "Default")
      (node (ref "CONN10") (pin "5") (pinfunction "5_5") (pintype "passive"))
      (node (ref "R32") (pin "2") (pinfunction "2_2") (pintype "passive"))
      (node (ref "R64") (pin "1") (pinfunction "1_1") (pintype "passive"))
    )
    (net (code "28") (name "D_IN_4") (class "Default")
      (node (ref "CONN10") (pin "7") (pinfunction "7_7") (pintype "passive"))
      (node (ref "R31") (pin "2") (pinfunction "2_2") (pintype "passive"))
      (node (ref "R63") (pin "1") (pinfunction "1_1") (pintype "passive"))
    )
    (net (code "29") (name "D_IN_5") (class "Default")
      (node (ref "CONN10") (pin "9") (pinfunction "9_9") (pintype "passive"))
      (node (ref "R30") (pin "2") (pinfunction "2_2") (pintype "passive"))
      (node (ref "R62") (pin "1") (pinfunction "1_1") (pintype "passive"))
    )
    (net (code "30") (name "D_IN_6") (class "Default")
      (node (ref "CONN10") (pin "11") (pinfunction "11_11") (pintype "passive"))
      (node (ref "R29") (pin "2") (pinfunction "2_2") (pintype "passive"))
      (node (ref "R61") (pin "1") (pinfunction "1_1") (pintype "passive"))
    )
    (net (code "31") (name "D_IN_7") (class "Default")
      (node (ref "CONN10") (pin "13") (pinfunction "13_13") (pintype "passive"))
      (node (ref "R28") (pin "2") (pinfunction "2_2") (pintype "passive"))
      (node (ref "R60") (pin "1") (pinfunction "1_1") (pintype "passive"))
    )
    (net (code "32") (name "D_IN_8") (class "Default")
      (node (ref "CONN10") (pin "15") (pinfunction "15_15") (pintype "passive"))
      (node (ref "R27") (pin "2") (pinfunction "2_2") (pintype "passive"))
      (node (ref "R59") (pin "1") (pinfunction "1_1") (pintype "passive"))
    )
    (net (code "33") (name "D_IN_9") (class "Default")
      (node (ref "CONN15") (pin "1") (pinfunction "1_1") (pintype "passive"))
      (node (ref "R26") (pin "2") (pinfunction "2_2") (pintype "passive"))
      (node (ref "R58") (pin "1") (pinfunction "1_1") (pintype "passive"))
    )
    (net (code "34") (name "D_IN_10") (class "Default")
      (node (ref "CONN15") (pin "3") (pinfunction "3_3") (pintype "passive"))
      (node (ref "R25") (pin "2") (pinfunction "2_2") (pintype "passive"))
      (node (ref "R57") (pin "1") (pinfunction "1_1") (pintype "passive"))
    )
    (net (code "35") (name "D_IN_11") (class "Default")
      (node (ref "CONN15") (pin "5") (pinfunction "5_5") (pintype "passive"))
      (node (ref "R24") (pin "2") (pinfunction "2_2") (pintype "passive"))
      (node (ref "R56") (pin "1") (pinfunction "1_1") (pintype "passive"))
    )
    (net (code "36") (name "D_IN_12") (class "Default")
      (node (ref "CONN15") (pin "7") (pinfunction "7_7") (pintype "passive"))
      (node (ref "R23") (pin "2") (pinfunction "2_2") (pintype "passive"))
      (node (ref "R55") (pin "1") (pinfunction "1_1") (pintype "passive"))
    )
    (net (code "37") (name "D_IN_13") (class "Default")
      (node (ref "CONN15") (pin "9") (pinfunction "9_9") (pintype "passive"))
      (node (ref "R22") (pin "2") (pinfunction "2_2") (pintype "passive"))
      (node (ref "R54") (pin "1") (pinfunction "1_1") (pintype "passive"))
    )
    (net (code "38") (name "D_IN_14") (class "Default")
      (node (ref "CONN15") (pin "11") (pinfunction "11_11") (pintype "passive"))
      (node (ref "R21") (pin "2") (pinfunction "2_2") (pintype "passive"))
      (node (ref "R53") (pin "1") (pinfunction "1_1") (pintype "passive"))
    )
    (net (code "39") (name "D_IN_15") (class "Default")
      (node (ref "CONN15") (pin "13") (pinfunction "13_13") (pintype "passive"))
      (node (ref "R20") (pin "2") (pinfunction "2_2") (pintype "passive"))
      (node (ref "R52") (pin "1") (pinfunction "1_1") (pintype "passive"))
    )
    (net (code "40") (name "D_IN_16") (class "Default")
      (node (ref "CONN15") (pin "15") (pinfunction "15_15") (pintype "passive"))
      (node (ref "R19") (pin "2") (pinfunction "2_2") (pintype "passive"))
      (node (ref "R51") (pin "1") (pinfunction "1_1") (pintype "passive"))
    )
    (net (code "41") (name "D_OUT_1_L") (class "Default")
      (node (ref "CONN9") (pin "1") (pinfunction "1_1") (pintype "passive"))
      (node (ref "R50") (pin "2") (pinfunction "2_2") (pintype "passive"))
    )
    (net (code "42") (name "D_OUT_1_R") (class "Default")
      (node (ref "R50") (pin "1") (pinfunction "1_1") (pintype "passive"))
      (node (ref "U2") (pin "26") (pinfunction "PD1(OC2B/SDA/INT1)_26") (pintype "bidirectional"))
    )
    (net (code "43") (name "D_OUT_2_L") (class "Default")
      (node (ref "CONN9") (pin "3") (pinfunction "3_3") (pintype "passive"))
      (node (ref "R49") (pin "2") (pinfunction "2_2") (pintype "passive"))
    )
    (net (code "44") (name "D_OUT_2_R") (class "Default")
      (node (ref "R49") (pin "1") (pinfunction "1_1") (pintype "passive"))
      (node (ref "U2") (pin "25") (pinfunction "PD0(OC0B/SCL/INT0)_25") (pintype "bidirectional"))
    )
    (net (code "45") (name "D_OUT_3_L") (class "Default")
      (node (ref "CONN9") (pin "5") (pinfunction "5_5") (pintype "passive"))
      (node (ref "R48") (pin "2") (pinfunction "2_2") (pintype "passive"))
    )
    (net (code "46") (name "D_OUT_3_R") (class "Default")
      (node (ref "R48") (pin "1") (pinfunction "1_1") (pintype "passive"))
      (node (ref "U2") (pin "19") (pinfunction "PE5(INT.5/TOSC2)_19") (pintype "bidirectional"))
    )
    (net (code "47") (name "D_OUT_4_L") (class "Default")
      (node (ref "CONN9") (pin "7") (pinfunction "7_7") (pintype "passive"))
      (node (ref "R47") (pin "2") (pinfunction "2_2") (pintype "passive"))
    )
    (net (code "48") (name "D_OUT_4_R") (class "Default")
      (node (ref "R47") (pin "1") (pinfunction "1_1") (pintype "passive"))
      (node (ref "U2") (pin "18") (pinfunction "PE4(INT4/TOSC1)_18") (pintype "bidirectional"))
    )
    (net (code "49") (name "D_OUT_5_L") (class "Default")
      (node (ref "CONN9") (pin "9") (pinfunction "9_9") (pintype "passive"))
      (node (ref "R46") (pin "2") (pinfunction "2_2") (pintype "passive"))
    )
    (net (code "50") (name "D_OUT_5_R") (class "Default")
      (node (ref "R46") (pin "1") (pinfunction "1_1") (pintype "passive"))
      (node (ref "U2") (pin "17") (pinfunction "PB7(PCINT7/OC.1C)_17") (pintype "bidirectional"))
    )
    (net (code "51") (name "D_OUT_6_L") (class "Default")
      (node (ref "CONN9") (pin "11") (pinfunction "11_11") (pintype "passive"))
      (node (ref "R45") (pin "2") (pinfunction "2_2") (pintype "passive"))
    )
    (net (code "52") (name "D_OUT_6_R") (class "Default")
      (node (ref "R45") (pin "1") (pinfunction "1_1") (pintype "passive"))
      (node (ref "U2") (pin "16") (pinfunction "PB6(PCINT6/OC.1B)_16") (pintype "bidirectional"))
    )
    (net (code "53") (name "D_OUT_7_L") (class "Default")
      (node (ref "CONN9") (pin "13") (pinfunction "13_13") (pintype "passive"))
      (node (ref "R44") (pin "2") (pinfunction "2_2") (pintype "passive"))
    )
    (net (code "54") (name "D_OUT_7_R") (class "Default")
      (node (ref "R44") (pin "1") (pinfunction "1_1") (pintype "passive"))
      (node (ref "U2") (pin "15") (pinfunction "PB5(PCINT5/OC.1A)_15") (pintype "bidirectional"))
    )
    (net (code "55") (name "D_OUT_8_L") (class "Default")
      (node (ref "CONN9") (pin "15") (pinfunction "15_15") (pintype "passive"))
      (node (ref "R43") (pin "2") (pinfunction "2_2") (pintype "passive"))
    )
    (net (code "56") (name "D_OUT_8_R") (class "Default")
      (node (ref "R43") (pin "1") (pinfunction "1_1") (pintype "passive"))
      (node (ref "U2") (pin "14") (pinfunction "PB4(PCINT4/OC.2A)_14") (pintype "bidirectional"))
    )
    (net (code "57") (name "D_OUT_9_L") (class "Default")
      (node (ref "CONN16") (pin "1") (pinfunction "1_1") (pintype "passive"))
      (node (ref "R42") (pin "1") (pinfunction "1_1") (pintype "passive"))
    )
    (net (code "58") (name "D_OUT_9_R") (class "Default")
      (node (ref "R42") (pin "2") (pinfunction "2_2") (pintype "passive"))
      (node (ref "U2") (pin "33") (pinfunction "PE0(~{WR})_33") (pintype "bidirectional"))
    )
    (net (code "59") (name "D_OUT_10_L") (class "Default")
      (node (ref "CONN16") (pin "3") (pinfunction "3_3") (pintype "passive"))
      (node (ref "R41") (pin "1") (pinfunction "1_1") (pintype "passive"))
    )
    (net (code "60") (name "D_OUT_10_R") (class "Default")
      (node (ref "R41") (pin "2") (pinfunction "2_2") (pintype "passive"))
      (node (ref "U2") (pin "34") (pinfunction "PE1(~{RD})_34") (pintype "bidirectional"))
    )
    (net (code "61") (name "D_OUT_11_L") (class "Default")
      (node (ref "CONN16") (pin "5") (pinfunction "5_5") (pintype "passive"))
      (node (ref "R40") (pin "1") (pinfunction "1_1") (pintype "passive"))
    )
    (net (code "62") (name "D_OUT_11_R") (class "Default")
      (node (ref "R40") (pin "2") (pinfunction "2_2") (pintype "passive"))
      (node (ref "U2") (pin "35") (pinfunction "PC0(A8)_35") (pintype "bidirectional"))
    )
    (net (code "63") (name "D_OUT_12_L") (class "Default")
      (node (ref "CONN16") (pin "7") (pinfunction "7_7") (pintype "passive"))
      (node (ref "R39") (pin "1") (pinfunction "1_1") (pintype "passive"))
    )
    (net (code "64") (name "D_OUT_12_R") (class "Default")
      (node (ref "R39") (pin "2") (pinfunction "2_2") (pintype "passive"))
      (node (ref "U2") (pin "36") (pinfunction "PC1(A9)_36") (pintype "bidirectional"))
    )
    (net (code "65") (name "D_OUT_13_L") (class "Default")
      (node (ref "CONN16") (pin "9") (pinfunction "9_9") (pintype "passive"))
      (node (ref "R38") (pin "1") (pinfunction "1_1") (pintype "passive"))
    )
    (net (code "66") (name "D_OUT_13_R") (class "Default")
      (node (ref "R38") (pin "2") (pinfunction "2_2") (pintype "passive"))
      (node (ref "U2") (pin "37") (pinfunction "PC2(A10)_37") (pintype "bidirectional"))
    )
    (net (code "67") (name "D_OUT_14_L") (class "Default")
      (node (ref "CONN16") (pin "11") (pinfunction "11_11") (pintype "passive"))
      (node (ref "R37") (pin "1") (pinfunction "1_1") (pintype "passive"))
    )
    (net (code "68") (name "D_OUT_14_R") (class "Default")
      (node (ref "R37") (pin "2") (pinfunction "2_2") (pintype "passive"))
      (node (ref "U2") (pin "38") (pinfunction "PC3(A11/T.3)_38") (pintype "bidirectional"))
    )
    (net (code "69") (name "D_OUT_15_L") (class "Default")
      (node (ref "CONN16") (pin "13") (pinfunction "13_13") (pintype "passive"))
      (node (ref "R36") (pin "1") (pinfunction "1_1") (pintype "passive"))
    )
    (net (code "70") (name "D_OUT_15_R") (class "Default")
      (node (ref "R36") (pin "2") (pinfunction "2_2") (pintype "passive"))
      (node (ref "U2") (pin "39") (pinfunction "PC4(A12/OC.3C)_39") (pintype "bidirectional"))
    )
    (net (code "71") (name "D_OUT_16_L") (class "Default")
      (node (ref "CONN16") (pin "15") (pinfunction "15_15") (pintype "passive"))
      (node (ref "R35") (pin "1") (pinfunction "1_1") (pintype "passive"))
    )
    (net (code "72") (name "D_OUT_16_R") (class "Default")
      (node (ref "R35") (pin "2") (pinfunction "2_2") (pintype "passive"))
      (node (ref "U2") (pin "40") (pinfunction "PC5(A13/OC.3A)_40") (pintype "bidirectional"))
    )
    (net (code "73") (name "D_OUT_17") (class "Default")
      (node (ref "R76") (pin "1") (pinfunction "1_1") (pintype "passive"))
      (node (ref "U2") (pin "31") (pinfunction "PD6(T1)_31") (pintype "bidirectional"))
    )
    (net (code "74") (name "D_OUT_17_HV") (class "Default")
      (node (ref "CONN5") (pin "2") (pinfunction "2_2") (pintype "passive"))
      (node (ref "D14") (pin "3") (pinfunction "A_3") (pintype "passive"))
      (node (ref "Q5") (pin "4") (pinfunction "D_4") (pintype "passive"))
    )
    (net (code "75") (name "D_OUT_18") (class "Default")
      (node (ref "R75") (pin "1") (pinfunction "1_1") (pintype "passive"))
      (node (ref "U2") (pin "32") (pinfunction "PD7(T0)_32") (pintype "bidirectional"))
    )
    (net (code "76") (name "D_OUT_18_HV") (class "Default")
      (node (ref "CONN5") (pin "4") (pinfunction "4_4") (pintype "passive"))
      (node (ref "D14") (pin "4") (pinfunction "A_4") (pintype "passive"))
      (node (ref "Q5") (pin "6") (pinfunction "D_6") (pintype "passive"))
    )
    (net (code "77") (name "D_OUT_19") (class "Default")
      (node (ref "R78") (pin "1") (pinfunction "1_1") (pintype "passive"))
      (node (ref "U2") (pin "29") (pinfunction "PD4(ICP1)_29") (pintype "bidirectional"))
    )
    (net (code "78") (name "D_OUT_19_HV") (class "Default")
      (node (ref "CONN5") (pin "8") (pinfunction "8_8") (pintype "passive"))
      (node (ref "D12") (pin "3") (pinfunction "A_3") (pintype "passive"))
      (node (ref "Q2") (pin "4") (pinfunction "D_4") (pintype "passive"))
    )
    (net (code "79") (name "D_OUT_20") (class "Default")
      (node (ref "R77") (pin "1") (pinfunction "1_1") (pintype "passive"))
      (node (ref "U2") (pin "30") (pinfunction "PD5(XCK1)_30") (pintype "bidirectional"))
    )
    (net (code "80") (name "D_OUT_20_HV") (class "Default")
      (node (ref "CONN5") (pin "6") (pinfunction "6_6") (pintype "passive"))
      (node (ref "D12") (pin "4") (pinfunction "A_4") (pintype "passive"))
      (node (ref "Q2") (pin "6") (pinfunction "D_6") (pintype "passive"))
    )
    (net (code "81") (name "GND") (class "Default")
      (node (ref "C1") (pin "1") (pinfunction "1_1") (pintype "passive"))
      (node (ref "C10") (pin "2") (pinfunction "2_2") (pintype "passive"))
      (node (ref "C11") (pin "1") (pinfunction "1_1") (pintype "passive"))
      (node (ref "C12") (pin "1") (pinfunction "1_1") (pintype "passive"))
      (node (ref "C13") (pin "2") (pinfunction "2_2") (pintype "passive"))
      (node (ref "C14") (pin "1") (pinfunction "1_1") (pintype "passive"))
      (node (ref "C15") (pin "1") (pinfunction "1_1") (pintype "passive"))
      (node (ref "C16") (pin "2") (pinfunction "2_2") (pintype "passive"))
      (node (ref "C17") (pin "2") (pinfunction "2_2") (pintype "passive"))
      (node (ref "C18") (pin "2") (pinfunction "2_2") (pintype "passive"))
      (node (ref "C2") (pin "2") (pinfunction "2_2") (pintype "passive"))
      (node (ref "C3") (pin "2") (pinfunction "2_2") (pintype "passive"))
      (node (ref "C4") (pin "2") (pinfunction "2_2") (pintype "passive"))
      (node (ref "C5") (pin "2") (pinfunction "2_2") (pintype "passive"))
      (node (ref "C6") (pin "2") (pinfunction "2_2") (pintype "passive"))
      (node (ref "C7") (pin "2") (pinfunction "2_2") (pintype "passive"))
      (node (ref "C8") (pin "1") (pinfunction "1_1") (pintype "passive"))
      (node (ref "C9") (pin "2") (pinfunction "2_2") (pintype "passive"))
      (node (ref "CONN10") (pin "10") (pinfunction "10_10") (pintype "passive"))
      (node (ref "CONN10") (pin "12") (pinfunction "12_12") (pintype "passive"))
      (node (ref "CONN10") (pin "14") (pinfunction "14_14") (pintype "passive"))
      (node (ref "CONN10") (pin "16") (pinfunction "16_16") (pintype "passive"))
      (node (ref "CONN10") (pin "2") (pinfunction "2_2") (pintype "passive"))
      (node (ref "CONN10") (pin "4") (pinfunction "4_4") (pintype "passive"))
      (node (ref "CONN10") (pin "6") (pinfunction "6_6") (pintype "passive"))
      (node (ref "CONN10") (pin "8") (pinfunction "8_8") (pintype "passive"))
      (node (ref "CONN13") (pin "1") (pinfunction "1_1") (pintype "passive"))
      (node (ref "CONN13") (pin "2") (pinfunction "2_2") (pintype "passive"))
      (node (ref "CONN13") (pin "3") (pinfunction "3_3") (pintype "passive"))
      (node (ref "CONN13") (pin "4") (pinfunction "4_4") (pintype "passive"))
      (node (ref "CONN13") (pin "5") (pinfunction "5_5") (pintype "passive"))
      (node (ref "CONN13") (pin "6") (pinfunction "6_6") (pintype "passive"))
      (node (ref "CONN13") (pin "7") (pinfunction "7_7") (pintype "passive"))
      (node (ref "CONN13") (pin "8") (pinfunction "8_8") (pintype "passive"))
      (node (ref "CONN14") (pin "1") (pinfunction "1_1") (pintype "passive"))
      (node (ref "CONN14") (pin "2") (pinfunction "2_2") (pintype "passive"))
      (node (ref "CONN14") (pin "3") (pinfunction "3_3") (pintype "passive"))
      (node (ref "CONN14") (pin "4") (pinfunction "4_4") (pintype "passive"))
      (node (ref "CONN14") (pin "5") (pinfunction "5_5") (pintype "passive"))
      (node (ref "CONN14") (pin "6") (pinfunction "6_6") (pintype "passive"))
      (node (ref "CONN14") (pin "7") (pinfunction "7_7") (pintype "passive"))
      (node (ref "CONN14") (pin "8") (pinfunction "8_8") (pintype "passive"))
      (node (ref "CONN15") (pin "10") (pinfunction "10_10") (pintype "passive"))
      (node (ref "CONN15") (pin "12") (pinfunction "12_12") (pintype "passive"))
      (node (ref "CONN15") (pin "14") (pinfunction "14_14") (pintype "passive"))
      (node (ref "CONN15") (pin "16") (pinfunction "16_16") (pintype "passive"))
      (node (ref "CONN15") (pin "2") (pinfunction "2_2") (pintype "passive"))
      (node (ref "CONN15") (pin "4") (pinfunction "4_4") (pintype "passive"))
      (node (ref "CONN15") (pin "6") (pinfunction "6_6") (pintype "passive"))
      (node (ref "CONN15") (pin "8") (pinfunction "8_8") (pintype "passive"))
      (node (ref "CONN16") (pin "10") (pinfunction "10_10") (pintype "passive"))
      (node (ref "CONN16") (pin "12") (pinfunction "12_12") (pintype "passive"))
      (node (ref "CONN16") (pin "14") (pinfunction "14_14") (pintype "passive"))
      (node (ref "CONN16") (pin "16") (pinfunction "16_16") (pintype "passive"))
      (node (ref "CONN16") (pin "2") (pinfunction "2_2") (pintype "passive"))
      (node (ref "CONN16") (pin "4") (pinfunction "4_4") (pintype "passive"))
      (node (ref "CONN16") (pin "6") (pinfunction "6_6") (pintype "passive"))
      (node (ref "CONN16") (pin "8") (pinfunction "8_8") (pintype "passive"))
      (node (ref "CONN2") (pin "2") (pinfunction "2_2") (pintype "passive"))
      (node (ref "CONN9") (pin "10") (pinfunction "10_10") (pintype "passive"))
      (node (ref "CONN9") (pin "12") (pinfunction "12_12") (pintype "passive"))
      (node (ref "CONN9") (pin "14") (pinfunction "14_14") (pintype "passive"))
      (node (ref "CONN9") (pin "16") (pinfunction "16_16") (pintype "passive"))
      (node (ref "CONN9") (pin "2") (pinfunction "2_2") (pintype "passive"))
      (node (ref "CONN9") (pin "4") (pinfunction "4_4") (pintype "passive"))
      (node (ref "CONN9") (pin "6") (pinfunction "6_6") (pintype "passive"))
      (node (ref "CONN9") (pin "8") (pinfunction "8_8") (pintype "passive"))
      (node (ref "D10") (pin "C") (pinfunction "C_C") (pintype "passive"))
      (node (ref "D11") (pin "C") (pinfunction "C_C") (pintype "passive"))
      (node (ref "D2") (pin "1") (pinfunction "GND_1") (pintype "passive"))
      (node (ref "D6") (pin "C") (pinfunction "C_C") (pintype "passive"))
      (node (ref "D7") (pin "C") (pinfunction "C_C") (pintype "passive"))
      (node (ref "D8") (pin "C") (pinfunction "C_C") (pintype "passive"))
      (node (ref "D9") (pin "C") (pinfunction "C_C") (pintype "passive"))
      (node (ref "EXT") (pin "GND@1") (pinfunction "GND_GND@1") (pintype "bidirectional"))
      (node (ref "EXT") (pin "GND@2") (pinfunction "GNDBREAK_GND@2") (pintype "bidirectional"))
      (node (ref "ICSP") (pin "6") (pinfunction "6_6") (pintype "passive"))
      (node (ref "L1") (pin "1") (pinfunction "1_1") (pintype "passive"))
      (node (ref "Q1") (pin "1") (pinfunction "G_1") (pintype "passive"))
      (node (ref "Q2") (pin "2") (pinfunction "S_2") (pintype "passive"))
      (node (ref "Q2") (pin "5") (pinfunction "S_5") (pintype "passive"))
      (node (ref "Q5") (pin "2") (pinfunction "S_2") (pintype "passive"))
      (node (ref "Q5") (pin "5") (pinfunction "S_5") (pintype "passive"))
      (node (ref "R12") (pin "2") (pinfunction "2_2") (pintype "passive"))
      (node (ref "R67") (pin "2") (pinfunction "2_2") (pintype "passive"))
      (node (ref "R68") (pin "2") (pinfunction "2_2") (pintype "passive"))
      (node (ref "R69") (pin "2") (pinfunction "2_2") (pintype "passive"))
      (node (ref "R70") (pin "2") (pinfunction "2_2") (pintype "passive"))
      (node (ref "R71") (pin "1") (pinfunction "1_1") (pintype "passive"))
      (node (ref "R72") (pin "1") (pinfunction "1_1") (pintype "passive"))
      (node (ref "TSCREEN") (pin "2") (pinfunction "2_2") (pintype "passive"))
      (node (ref "U1") (pin "5") (pinfunction "GND_5") (pintype "power_in"))
      (node (ref "U2") (pin "22") (pinfunction "GND_22") (pintype "power_in"))
      (node (ref "U2") (pin "53") (pinfunction "GND_53") (pintype "power_in"))
      (node (ref "U2") (pin "6") (pinfunction "UGND_6") (pintype "power_in"))
      (node (ref "U2") (pin "63") (pinfunction "GND_63") (pintype "power_in"))
      (node (ref "U3") (pin "12") (pinfunction "GND_12") (pintype "passive"))
      (node (ref "U3") (pin "15") (pinfunction "~{E}_15") (pintype "input"))
      (node (ref "U4") (pin "15") (pinfunction "~{CE}_15") (pintype "input"))
      (node (ref "U4") (pin "8") (pinfunction "GND_8") (pintype "power_in"))
      (node (ref "U5") (pin "15") (pinfunction "~{CE}_15") (pintype "input"))
      (node (ref "U5") (pin "8") (pinfunction "GND_8") (pintype "power_in"))
      (node (ref "USB") (pin "A1") (pinfunction "GND_A1") (pintype "passive"))
      (node (ref "USB") (pin "A12") (pinfunction "GND_A12") (pintype "passive"))
      (node (ref "USB") (pin "B1") (pinfunction "GND_B1") (pintype "passive"))
      (node (ref "USB") (pin "B12") (pinfunction "GND_B12") (pintype "passive"))
      (node (ref "VR1") (pin "1") (pinfunction "GND_1") (pintype "passive"))
      (node (ref "VR2") (pin "2") (pinfunction "GND_2") (pintype "passive"))
    )
    (net (code "82") (name "LED_IND_DIN_IN") (class "Default")
      (node (ref "R16") (pin "1") (pinfunction "1_1") (pintype "passive"))
      (node (ref "U2") (pin "46") (pinfunction "PA5(AD5)_46") (pintype "bidirectional"))
    )
    (net (code "83") (name "LED_IND_DIN_OUT") (class "Default")
      (node (ref "R15") (pin "1") (pinfunction "1_1") (pintype "passive"))
      (node (ref "U2") (pin "45") (pinfunction "PA6(AD6)_45") (pintype "bidirectional"))
    )
    (net (code "84") (name "LED_IND_USB_IN") (class "Default")
      (node (ref "R18") (pin "1") (pinfunction "1_1") (pintype "passive"))
      (node (ref "U2") (pin "48") (pinfunction "PA3(AD3)_48") (pintype "bidirectional"))
    )
    (net (code "85") (name "LED_IND_USB_OUT") (class "Default")
      (node (ref "R17") (pin "1") (pinfunction "1_1") (pintype "passive"))
      (node (ref "U2") (pin "47") (pinfunction "PA4(AD4)_47") (pintype "bidirectional"))
    )
    (net (code "86") (name "MISO") (class "Default")
      (node (ref "ICSP") (pin "1") (pinfunction "1_1") (pintype "passive"))
      (node (ref "U2") (pin "13") (pinfunction "PB3(PDO/PCINT3/MISO)_13") (pintype "bidirectional"))
    )
    (net (code "87") (name "MOSI") (class "Default")
      (node (ref "ICSP") (pin "4") (pinfunction "4_4") (pintype "passive"))
      (node (ref "U2") (pin "12") (pinfunction "PB2(PDI/PCINT2/MOSI)_12") (pintype "bidirectional"))
    )
    (net (code "88") (name "MUX_COMMON") (class "Default")
      (node (ref "R10") (pin "2") (pinfunction "2_2") (pintype "passive"))
      (node (ref "U3") (pin "1") (pinfunction "Z_1") (pintype "bidirectional"))
    )
    (net (code "89") (name "MUX_S0") (class "Default")
      (node (ref "U2") (pin "41") (pinfunction "PC6(A14/OC.3A)_41") (pintype "bidirectional"))
      (node (ref "U3") (pin "10") (pinfunction "S0_10") (pintype "input"))
    )
    (net (code "90") (name "MUX_S1") (class "Default")
      (node (ref "U2") (pin "42") (pinfunction "PC7(A15/IC.3/CLKO)_42") (pintype "bidirectional"))
      (node (ref "U3") (pin "11") (pinfunction "S1_11") (pintype "input"))
    )
    (net (code "91") (name "MUX_S2") (class "Default")
      (node (ref "U2") (pin "43") (pinfunction "PE2(ALE/~{HWB})_43") (pintype "bidirectional"))
      (node (ref "U3") (pin "14") (pinfunction "S2_14") (pintype "input"))
    )
    (net (code "92") (name "MUX_S3") (class "Default")
      (node (ref "U2") (pin "44") (pinfunction "PA7(AD7)_44") (pintype "bidirectional"))
      (node (ref "U3") (pin "13") (pinfunction "S3_13") (pintype "input"))
    )
    (net (code "93") (name "Net-(CONN2-Pad4)") (class "Default")
      (node (ref "CONN2") (pin "4") (pinfunction "4_4") (pintype "bidirectional"))
      (node (ref "R4") (pin "1") (pinfunction "1_1") (pintype "passive"))
    )
    (net (code "94") (name "Net-(CONN2-Pad5)") (class "Default")
      (node (ref "CONN2") (pin "5") (pinfunction "5_5") (pintype "bidirectional"))
      (node (ref "R3") (pin "1") (pinfunction "1_1") (pintype "passive"))
    )
    (net (code "95") (name "Net-(CONN3-Pad4)") (class "Default")
      (node (ref "CONN3") (pin "4") (pinfunction "4_4") (pintype "bidirectional"))
      (node (ref "R5") (pin "1") (pinfunction "1_1") (pintype "passive"))
    )
    (net (code "96") (name "Net-(D6-PadA)") (class "Default")
      (node (ref "D6") (pin "A") (pinfunction "A_A") (pintype "passive"))
      (node (ref "R13") (pin "2") (pinfunction "2_2") (pintype "passive"))
    )
    (net (code "97") (name "Net-(D7-PadA)") (class "Default")
      (node (ref "D7") (pin "A") (pinfunction "A_A") (pintype "passive"))
      (node (ref "R14") (pin "2") (pinfunction "2_2") (pintype "passive"))
    )
    (net (code "98") (name "Net-(D8-PadA)") (class "Default")
      (node (ref "D8") (pin "A") (pinfunction "A_A") (pintype "passive"))
      (node (ref "R15") (pin "2") (pinfunction "2_2") (pintype "passive"))
    )
    (net (code "99") (name "Net-(D9-PadA)") (class "Default")
      (node (ref "D9") (pin "A") (pinfunction "A_A") (pintype "passive"))
      (node (ref "R16") (pin "2") (pinfunction "2_2") (pintype "passive"))
    )
    (net (code "100") (name "Net-(D10-PadA)") (class "Default")
      (node (ref "D10") (pin "A") (pinfunction "A_A") (pintype "passive"))
      (node (ref "R17") (pin "2") (pinfunction "2_2") (pintype "passive"))
    )
    (net (code "101") (name "Net-(D11-PadA)") (class "Default")
      (node (ref "D11") (pin "A") (pinfunction "A_A") (pintype "passive"))
      (node (ref "R18") (pin "2") (pinfunction "2_2") (pintype "passive"))
    )
    (net (code "102") (name "Net-(EXT-PWR)") (class "Default")
      (node (ref "EXT") (pin "PWR1") (pinfunction "PWR_PWR1") (pintype "bidirectional"))
      (node (ref "Q1") (pin "2") (pinfunction "S_2") (pintype "passive"))
    )
    (net (code "103") (name "Net-(F1-Pad2)") (class "Default")
      (node (ref "F1") (pin "2") (pinfunction "2_2") (pintype "passive"))
      (node (ref "USB") (pin "A4") (pinfunction "VBUS_A4") (pintype "power_in"))
      (node (ref "USB") (pin "A9") (pinfunction "VBUS_A9") (pintype "power_in"))
      (node (ref "USB") (pin "B4") (pinfunction "VBUS_B4") (pintype "power_in"))
      (node (ref "USB") (pin "B9") (pinfunction "VBUS_B9") (pintype "power_in"))
    )
    (net (code "104") (name "Net-(L1-Pad2)") (class "Default")
      (node (ref "L1") (pin "2") (pinfunction "2_2") (pintype "passive"))
      (node (ref "USB") (pin "P1") (pinfunction "SHIELD_P1") (pintype "passive"))
      (node (ref "USB") (pin "P2") (pinfunction "SHIELD_P2") (pintype "passive"))
      (node (ref "USB") (pin "P3") (pinfunction "SHIELD_P3") (pintype "passive"))
      (node (ref "USB") (pin "P4") (pinfunction "SHIELD_P4") (pintype "passive"))
    )
    (net (code "105") (name "Net-(Q2A-G)") (class "Default")
      (node (ref "Q2") (pin "1") (pinfunction "G_1") (pintype "passive"))
      (node (ref "R68") (pin "1") (pinfunction "1_1") (pintype "passive"))
      (node (ref "R77") (pin "2") (pinfunction "2_2") (pintype "passive"))
    )
    (net (code "106") (name "Net-(Q2B-G)") (class "Default")
      (node (ref "Q2") (pin "3") (pinfunction "G_3") (pintype "passive"))
      (node (ref "R67") (pin "1") (pinfunction "1_1") (pintype "passive"))
      (node (ref "R78") (pin "2") (pinfunction "2_2") (pintype "passive"))
    )
    (net (code "107") (name "Net-(Q5A-G)") (class "Default")
      (node (ref "Q5") (pin "1") (pinfunction "G_1") (pintype "passive"))
      (node (ref "R70") (pin "1") (pinfunction "1_1") (pintype "passive"))
      (node (ref "R75") (pin "2") (pinfunction "2_2") (pintype "passive"))
    )
    (net (code "108") (name "Net-(Q5B-G)") (class "Default")
      (node (ref "Q5") (pin "3") (pinfunction "G_3") (pintype "passive"))
      (node (ref "R69") (pin "1") (pinfunction "1_1") (pintype "passive"))
      (node (ref "R76") (pin "2") (pinfunction "2_2") (pintype "passive"))
    )
    (net (code "109") (name "Net-(R3-Pad2)") (class "Default")
      (node (ref "R3") (pin "2") (pinfunction "2_2") (pintype "passive"))
      (node (ref "R6") (pin "1") (pinfunction "1_1") (pintype "passive"))
    )
    (net (code "110") (name "Net-(U1-A)") (class "Default")
      (node (ref "D1") (pin "C") (pinfunction "C_C") (pintype "passive"))
      (node (ref "R5") (pin "2") (pinfunction "2_2") (pintype "passive"))
      (node (ref "U1") (pin "2") (pinfunction "A_2") (pintype "passive"))
    )
    (net (code "111") (name "Net-(U1-C)") (class "Default")
      (node (ref "CONN3") (pin "5") (pinfunction "5_5") (pintype "bidirectional"))
      (node (ref "D1") (pin "A") (pinfunction "A_A") (pintype "passive"))
      (node (ref "U1") (pin "3") (pinfunction "C_3") (pintype "passive"))
    )
    (net (code "112") (name "Net-(U1-VO)") (class "Default")
      (node (ref "R8") (pin "2") (pinfunction "2_2") (pintype "passive"))
      (node (ref "R9") (pin "1") (pinfunction "1_1") (pintype "passive"))
      (node (ref "U1") (pin "6") (pinfunction "VO_6") (pintype "output"))
    )
    (net (code "113") (name "Net-(U2-PF0(ADC0))") (class "Default")
      (node (ref "R10") (pin "1") (pinfunction "1_1") (pintype "passive"))
      (node (ref "U2") (pin "61") (pinfunction "PF0(ADC0)_61") (pintype "bidirectional"))
    )
    (net (code "114") (name "Net-(U2-UCAP)") (class "Default")
      (node (ref "C11") (pin "2") (pinfunction "2_2") (pintype "passive"))
      (node (ref "U2") (pin "7") (pinfunction "UCAP_7") (pintype "bidirectional"))
    )
    (net (code "115") (name "Net-(U4-D0)") (class "Default")
      (node (ref "R23") (pin "1") (pinfunction "1_1") (pintype "passive"))
      (node (ref "U4") (pin "11") (pinfunction "D0_11") (pintype "input"))
    )
    (net (code "116") (name "Net-(U4-D1)") (class "Default")
      (node (ref "R24") (pin "1") (pinfunction "1_1") (pintype "passive"))
      (node (ref "U4") (pin "12") (pinfunction "D1_12") (pintype "input"))
    )
    (net (code "117") (name "Net-(U4-D2)") (class "Default")
      (node (ref "R25") (pin "1") (pinfunction "1_1") (pintype "passive"))
      (node (ref "U4") (pin "13") (pinfunction "D2_13") (pintype "input"))
    )
    (net (code "118") (name "Net-(U4-D3)") (class "Default")
      (node (ref "R26") (pin "1") (pinfunction "1_1") (pintype "passive"))
      (node (ref "U4") (pin "14") (pinfunction "D3_14") (pintype "input"))
    )
    (net (code "119") (name "Net-(U4-D4)") (class "Default")
      (node (ref "R22") (pin "1") (pinfunction "1_1") (pintype "passive"))
      (node (ref "U4") (pin "3") (pinfunction "D4_3") (pintype "input"))
    )
    (net (code "120") (name "Net-(U4-D5)") (class "Default")
      (node (ref "R21") (pin "1") (pinfunction "1_1") (pintype "passive"))
      (node (ref "U4") (pin "4") (pinfunction "D5_4") (pintype "input"))
    )
    (net (code "121") (name "Net-(U4-D6)") (class "Default")
      (node (ref "R20") (pin "1") (pinfunction "1_1") (pintype "passive"))
      (node (ref "U4") (pin "5") (pinfunction "D6_5") (pintype "input"))
    )
    (net (code "122") (name "Net-(U4-D7)") (class "Default")
      (node (ref "R19") (pin "1") (pinfunction "1_1") (pintype "passive"))
      (node (ref "U4") (pin "6") (pinfunction "D7_6") (pintype "input"))
    )
    (net (code "123") (name "Net-(U5-D0)") (class "Default")
      (node (ref "R31") (pin "1") (pinfunction "1_1") (pintype "passive"))
      (node (ref "U5") (pin "11") (pinfunction "D0_11") (pintype "input"))
    )
    (net (code "124") (name "Net-(U5-D1)") (class "Default")
      (node (ref "R32") (pin "1") (pinfunction "1_1") (pintype "passive"))
      (node (ref "U5") (pin "12") (pinfunction "D1_12") (pintype "input"))
    )
    (net (code "125") (name "Net-(U5-D2)") (class "Default")
      (node (ref "R33") (pin "1") (pinfunction "1_1") (pintype "passive"))
      (node (ref "U5") (pin "13") (pinfunction "D2_13") (pintype "input"))
    )
    (net (code "126") (name "Net-(U5-D3)") (class "Default")
      (node (ref "R34") (pin "1") (pinfunction "1_1") (pintype "passive"))
      (node (ref "U5") (pin "14") (pinfunction "D3_14") (pintype "input"))
    )
    (net (code "127") (name "Net-(U5-D4)") (class "Default")
      (node (ref "R30") (pin "1") (pinfunction "1_1") (pintype "passive"))
      (node (ref "U5") (pin "3") (pinfunction "D4_3") (pintype "input"))
    )
    (net (code "128") (name "Net-(U5-D5)") (class "Default")
      (node (ref "R29") (pin "1") (pinfunction "1_1") (pintype "passive"))
      (node (ref "U5") (pin "4") (pinfunction "D5_4") (pintype "input"))
    )
    (net (code "129") (name "Net-(U5-D6)") (class "Default")
      (node (ref "R28") (pin "1") (pinfunction "1_1") (pintype "passive"))
      (node (ref "U5") (pin "5") (pinfunction "D6_5") (pintype "input"))
    )
    (net (code "130") (name "Net-(U5-D7)") (class "Default")
      (node (ref "R27") (pin "1") (pinfunction "1_1") (pintype "passive"))
      (node (ref "U5") (pin "6") (pinfunction "D7_6") (pintype "input"))
    )
    (net (code "131") (name "Net-(USB-CC1)") (class "Default")
      (node (ref "R71") (pin "2") (pinfunction "2_2") (pintype "passive"))
      (node (ref "USB") (pin "A5") (pinfunction "CC1_A5") (pintype "bidirectional"))
    )
    (net (code "132") (name "Net-(USB-CC2)") (class "Default")
      (node (ref "R72") (pin "2") (pinfunction "2_2") (pintype "passive"))
      (node (ref "USB") (pin "B5") (pinfunction "CC2_B5") (pintype "bidirectional"))
    )
    (net (code "133") (name "RESET") (class "Default")
      (node (ref "ICSP") (pin "5") (pinfunction "5_5") (pintype "passive"))
      (node (ref "R7") (pin "1") (pinfunction "1_1") (pintype "passive"))
      (node (ref "U2") (pin "20") (pinfunction "~{RESET}_20") (pintype "bidirectional"))
    )
    (net (code "134") (name "SCK") (class "Default")
      (node (ref "ICSP") (pin "3") (pinfunction "3_3") (pintype "passive"))
      (node (ref "U2") (pin "11") (pinfunction "PB1(PCINT1/SCLK)_11") (pintype "bidirectional"))
    )
    (net (code "135") (name "SR_IN_CLOCK") (class "Default")
      (node (ref "U2") (pin "10") (pinfunction "PB0(SS/PCINT0)_10") (pintype "bidirectional"))
      (node (ref "U4") (pin "2") (pinfunction "CP_2") (pintype "bidirectional"))
      (node (ref "U5") (pin "2") (pinfunction "CP_2") (pintype "bidirectional"))
    )
    (net (code "136") (name "SR_IN_DAISY_OUT_1") (class "Default")
      (node (ref "U4") (pin "9") (pinfunction "Q7_9") (pintype "output"))
      (node (ref "U5") (pin "10") (pinfunction "DS_10") (pintype "bidirectional"))
    )
    (net (code "137") (name "SR_IN_DATA") (class "Default")
      (node (ref "U2") (pin "1") (pinfunction "PE6(INT.6/AIN.0)_1") (pintype "bidirectional"))
      (node (ref "U5") (pin "9") (pinfunction "Q7_9") (pintype "output"))
    )
    (net (code "138") (name "SR_IN_LATCH") (class "Default")
      (node (ref "U2") (pin "2") (pinfunction "PE7(INT.7/AIN.1/UVCON)_2") (pintype "bidirectional"))
      (node (ref "U4") (pin "1") (pinfunction "~{PL}_1") (pintype "input"))
      (node (ref "U5") (pin "1") (pinfunction "~{PL}_1") (pintype "input"))
    )
    (net (code "139") (name "UART_RX") (class "Default")
      (node (ref "R8") (pin "1") (pinfunction "1_1") (pintype "passive"))
      (node (ref "TSCREEN") (pin "4") (pinfunction "4_4") (pintype "passive"))
      (node (ref "U2") (pin "27") (pinfunction "PD2(RXD1/INT2)_27") (pintype "bidirectional"))
    )
    (net (code "140") (name "UART_TX") (class "Default")
      (node (ref "R6") (pin "2") (pinfunction "2_2") (pintype "passive"))
      (node (ref "TSCREEN") (pin "3") (pinfunction "3_3") (pintype "passive"))
      (node (ref "U2") (pin "28") (pinfunction "PD3(TXD1/INT3)_28") (pintype "bidirectional"))
    )
    (net (code "141") (name "VIN") (class "Default")
      (node (ref "C10") (pin "1") (pinfunction "1_1") (pintype "passive"))
      (node (ref "CONN5") (pin "1") (pinfunction "1_1") (pintype "passive"))
      (node (ref "CONN5") (pin "3") (pinfunction "3_3") (pintype "passive"))
      (node (ref "CONN5") (pin "5") (pinfunction "5_5") (pintype "passive"))
      (node (ref "CONN5") (pin "7") (pinfunction "7_7") (pintype "passive"))
      (node (ref "D12") (pin "1") (pinfunction "C_1") (pintype "passive"))
      (node (ref "D12") (pin "2") (pinfunction "C_2") (pintype "passive"))
      (node (ref "D14") (pin "1") (pinfunction "C_1") (pintype "passive"))
      (node (ref "D14") (pin "2") (pinfunction "C_2") (pintype "passive"))
      (node (ref "Q1") (pin "3") (pinfunction "D_3") (pintype "passive"))
      (node (ref "VR1") (pin "3") (pinfunction "VIN_3") (pintype "passive"))
    )
    (net (code "142") (name "VUSB") (class "Default")
      (node (ref "C7") (pin "1") (pinfunction "1_1") (pintype "passive"))
      (node (ref "C9") (pin "1") (pinfunction "1_1") (pintype "passive"))
      (node (ref "D2") (pin "4") (pinfunction "VCC_4") (pintype "passive"))
      (node (ref "D3") (pin "A") (pinfunction "A_A") (pintype "passive"))
      (node (ref "F1") (pin "1") (pinfunction "1_1") (pintype "passive"))
      (node (ref "R14") (pin "1") (pinfunction "1_1") (pintype "passive"))
    )
    (net (code "143") (name "XTAL1") (class "Default")
      (node (ref "C1") (pin "2") (pinfunction "2_2") (pintype "passive"))
      (node (ref "U2") (pin "24") (pinfunction "XTAL1_24") (pintype "input"))
      (node (ref "Y1") (pin "1") (pinfunction "1_1") (pintype "passive"))
    )
    (net (code "144") (name "XTAL2") (class "Default")
      (node (ref "C8") (pin "2") (pinfunction "2_2") (pintype "passive"))
      (node (ref "U2") (pin "23") (pinfunction "XTAL2_23") (pintype "input"))
      (node (ref "Y1") (pin "3") (pinfunction "2_3") (pintype "passive"))
    )
    (net (code "145") (name "unconnected-(CONN2-Pad1)") (class "Default")
      (node (ref "CONN2") (pin "1") (pinfunction "1_1") (pintype "bidirectional"))
    )
    (net (code "146") (name "unconnected-(CONN2-Pad3)") (class "Default")
      (node (ref "CONN2") (pin "3") (pinfunction "3_3") (pintype "bidirectional"))
    )
    (net (code "147") (name "unconnected-(CONN3-Pad1)") (class "Default")
      (node (ref "CONN3") (pin "1") (pinfunction "1_1") (pintype "bidirectional"))
    )
    (net (code "148") (name "unconnected-(CONN3-Pad2)") (class "Default")
      (node (ref "CONN3") (pin "2") (pinfunction "2_2") (pintype "passive"))
    )
    (net (code "149") (name "unconnected-(CONN3-Pad3)") (class "Default")
      (node (ref "CONN3") (pin "3") (pinfunction "3_3") (pintype "bidirectional"))
    )
    (net (code "150") (name "unconnected-(U2-PA0(AD0)-Pad51)") (class "Default")
      (node (ref "U2") (pin "51") (pinfunction "PA0(AD0)_51") (pintype "bidirectional"))
    )
    (net (code "151") (name "unconnected-(U2-PA1(AD1)-Pad50)") (class "Default")
      (node (ref "U2") (pin "50") (pinfunction "PA1(AD1)_50") (pintype "bidirectional"))
    )
    (net (code "152") (name "unconnected-(U2-PA2(AD2)-Pad49)") (class "Default")
      (node (ref "U2") (pin "49") (pinfunction "PA2(AD2)_49") (pintype "bidirectional"))
    )
    (net (code "153") (name "unconnected-(U2-PF1(ADC1)-Pad60)") (class "Default")
      (node (ref "U2") (pin "60") (pinfunction "PF1(ADC1)_60") (pintype "bidirectional"))
    )
    (net (code "154") (name "unconnected-(U2-PF2(ADC2)-Pad59)") (class "Default")
      (node (ref "U2") (pin "59") (pinfunction "PF2(ADC2)_59") (pintype "bidirectional"))
    )
    (net (code "155") (name "unconnected-(U2-PF3(ADC3)-Pad58)") (class "Default")
      (node (ref "U2") (pin "58") (pinfunction "PF3(ADC3)_58") (pintype "bidirectional"))
    )
    (net (code "156") (name "unconnected-(U2-PF4(ADC4{slash}TCK)-Pad57)") (class "Default")
      (node (ref "U2") (pin "57") (pinfunction "PF4(ADC4/TCK)_57") (pintype "bidirectional"))
    )
    (net (code "157") (name "unconnected-(U2-PF5(ADC5{slash}TMS)-Pad56)") (class "Default")
      (node (ref "U2") (pin "56") (pinfunction "PF5(ADC5/TMS)_56") (pintype "bidirectional"))
    )
    (net (code "158") (name "unconnected-(U2-PF6(ADC6{slash}TDO)-Pad55)") (class "Default")
      (node (ref "U2") (pin "55") (pinfunction "PF6(ADC6/TDO)_55") (pintype "bidirectional"))
    )
    (net (code "159") (name "unconnected-(U2-PF7(ADC7{slash}TDI)-Pad54)") (class "Default")
      (node (ref "U2") (pin "54") (pinfunction "PF7(ADC7/TDI)_54") (pintype "bidirectional"))
    )
    (net (code "160") (name "unconnected-(U4-DS-Pad10)") (class "Default")
      (node (ref "U4") (pin "10") (pinfunction "DS_10") (pintype "bidirectional"))
    )
    (net (code "161") (name "unconnected-(U4-~{Q7}-Pad7)") (class "Default")
      (node (ref "U4") (pin "7") (pinfunction "~{Q7}_7") (pintype "output"))
    )
    (net (code "162") (name "unconnected-(U5-~{Q7}-Pad7)") (class "Default")
      (node (ref "U5") (pin "7") (pinfunction "~{Q7}_7") (pintype "output"))
    )
    (net (code "163") (name "unconnected-(USB-SBU1-PadA8)") (class "Default")
      (node (ref "USB") (pin "A8") (pinfunction "SBU1_A8") (pintype "bidirectional"))
    )
    (net (code "164") (name "unconnected-(USB-SBU2-PadB8)") (class "Default")
      (node (ref "USB") (pin "B8") (pinfunction "SBU2_B8") (pintype "bidirectional"))
    )
  )
)
